# axiom_beta_plugin_module_TE0714_SDI_v0_6.net
KiCad netlist of a schematic drawn in EAGLE
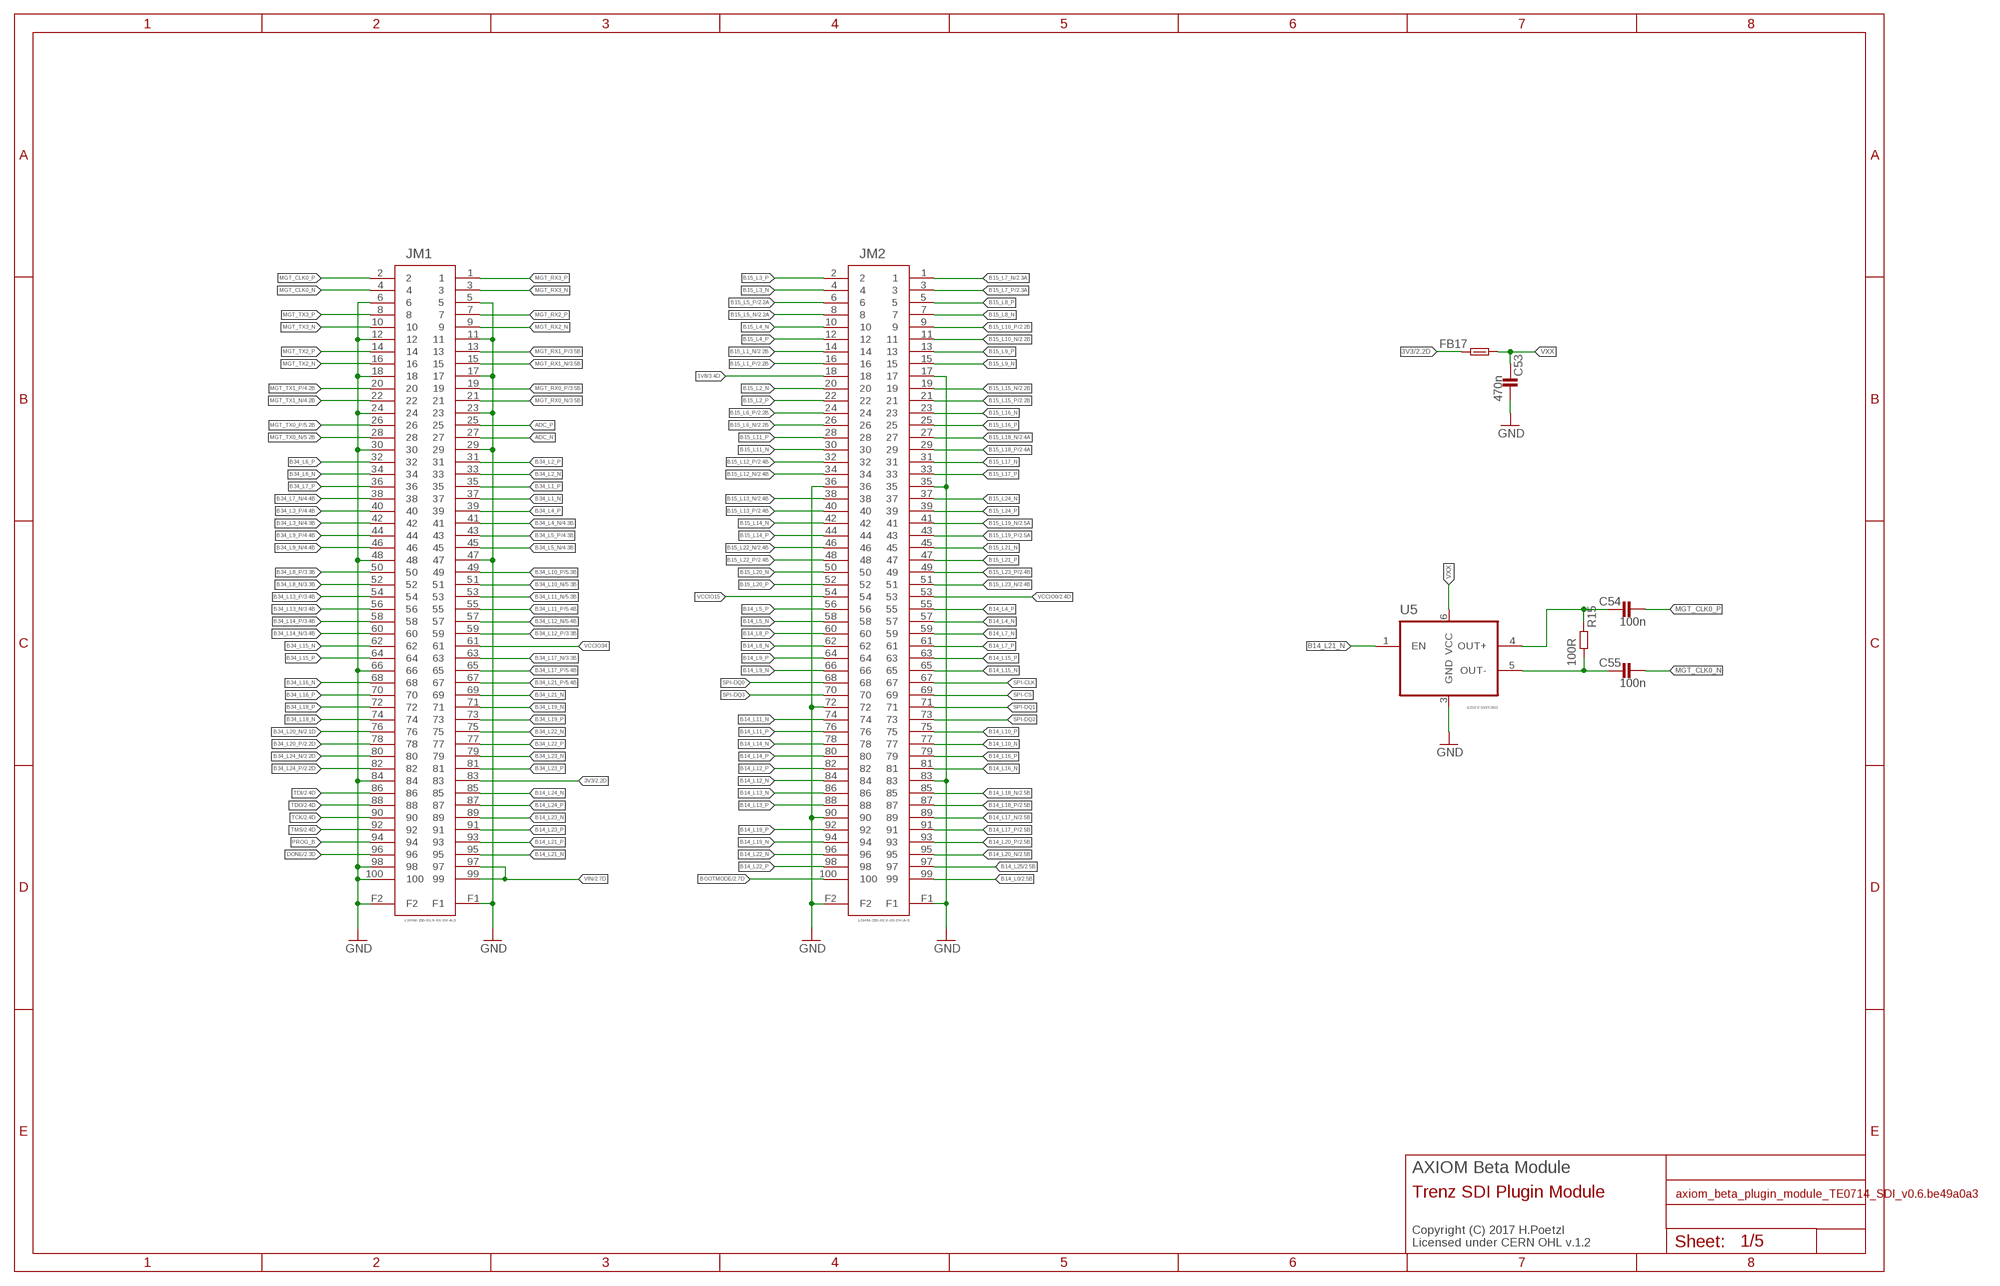
[diagram p0: schematic, sheet 1]
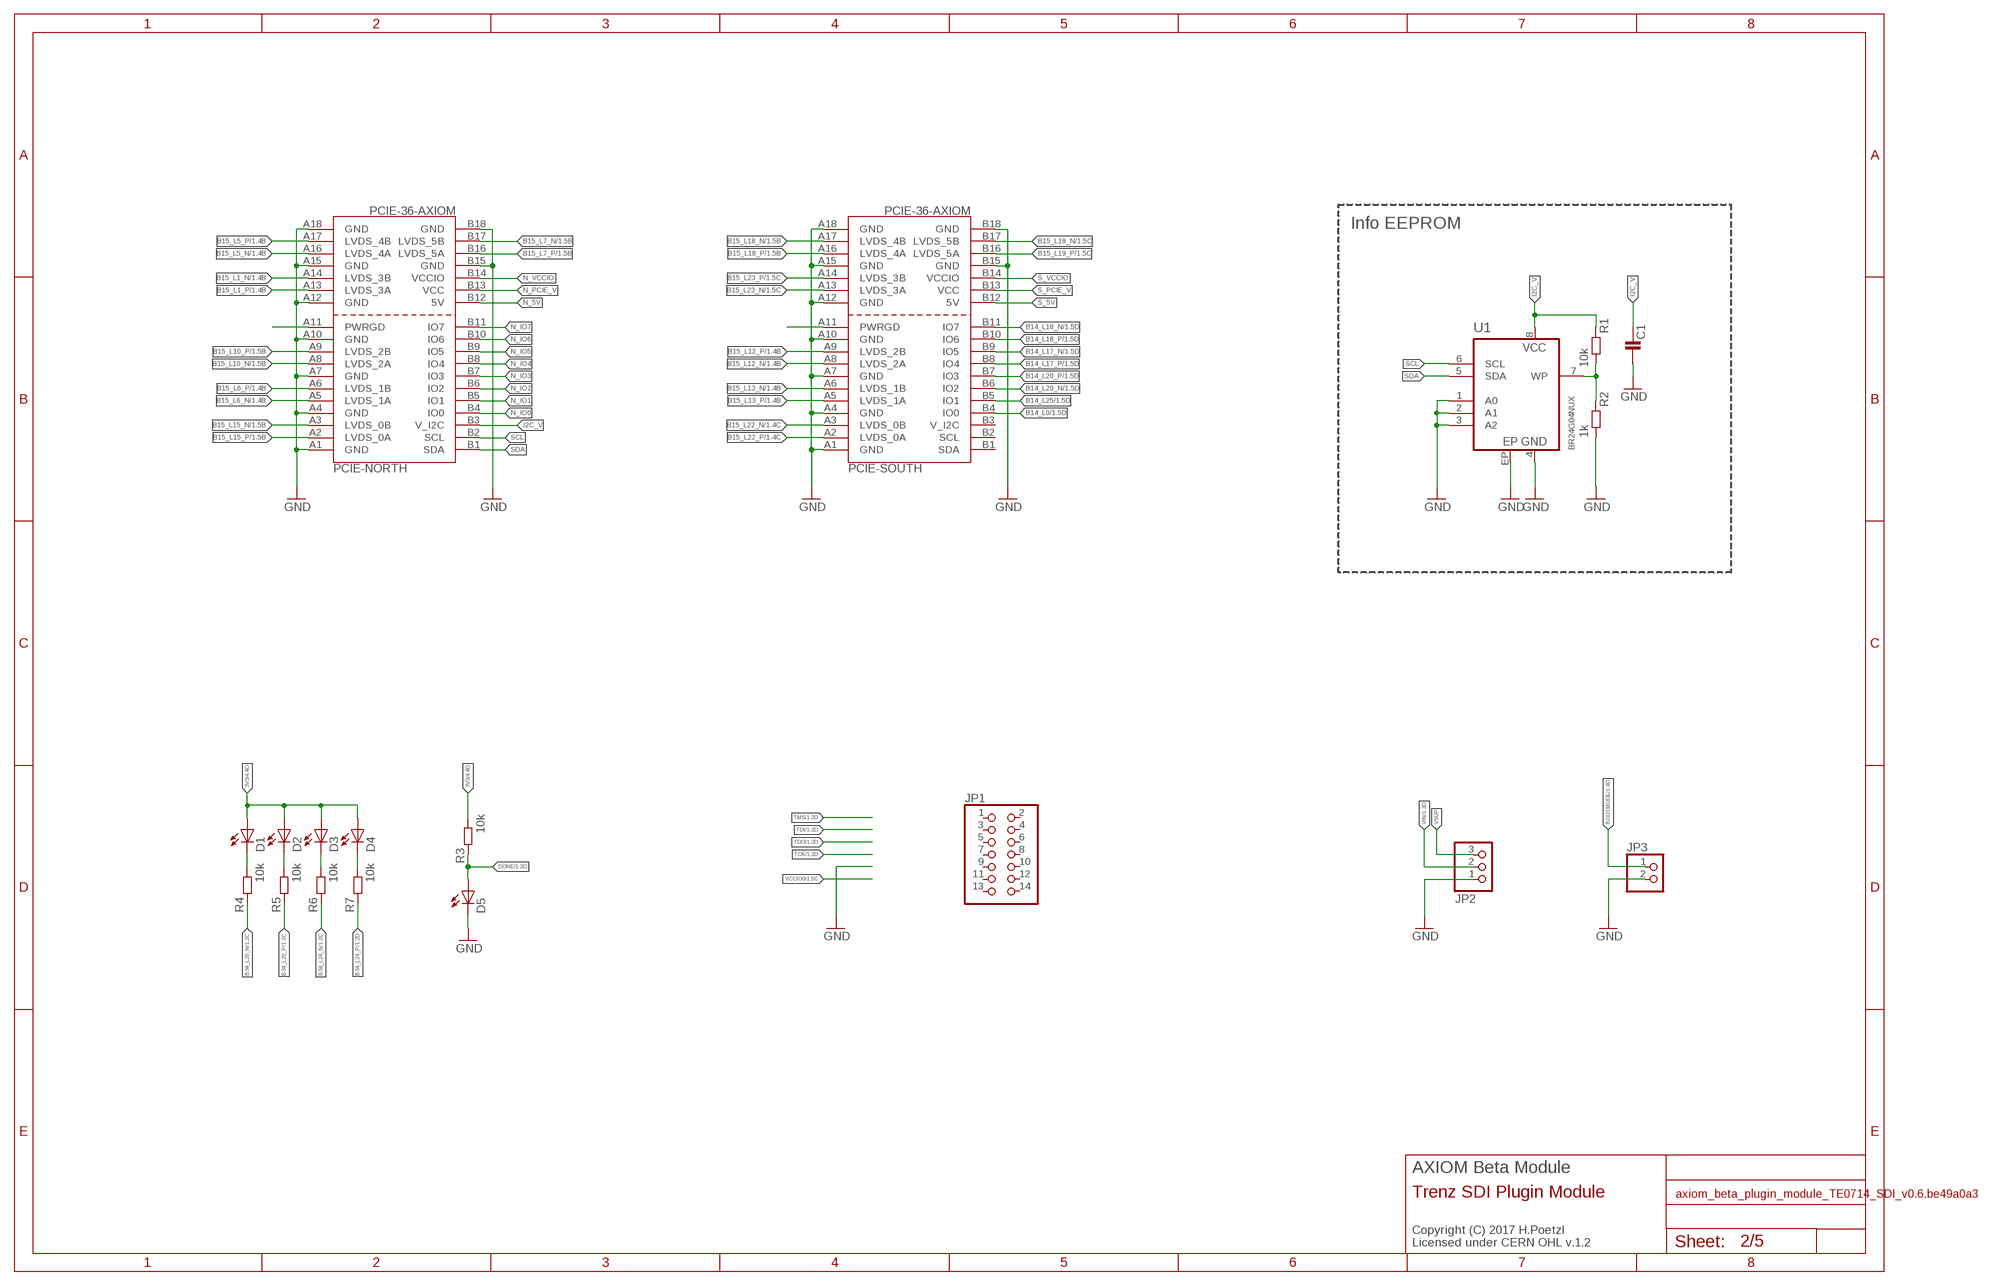
[diagram p1: schematic, sheet 2]
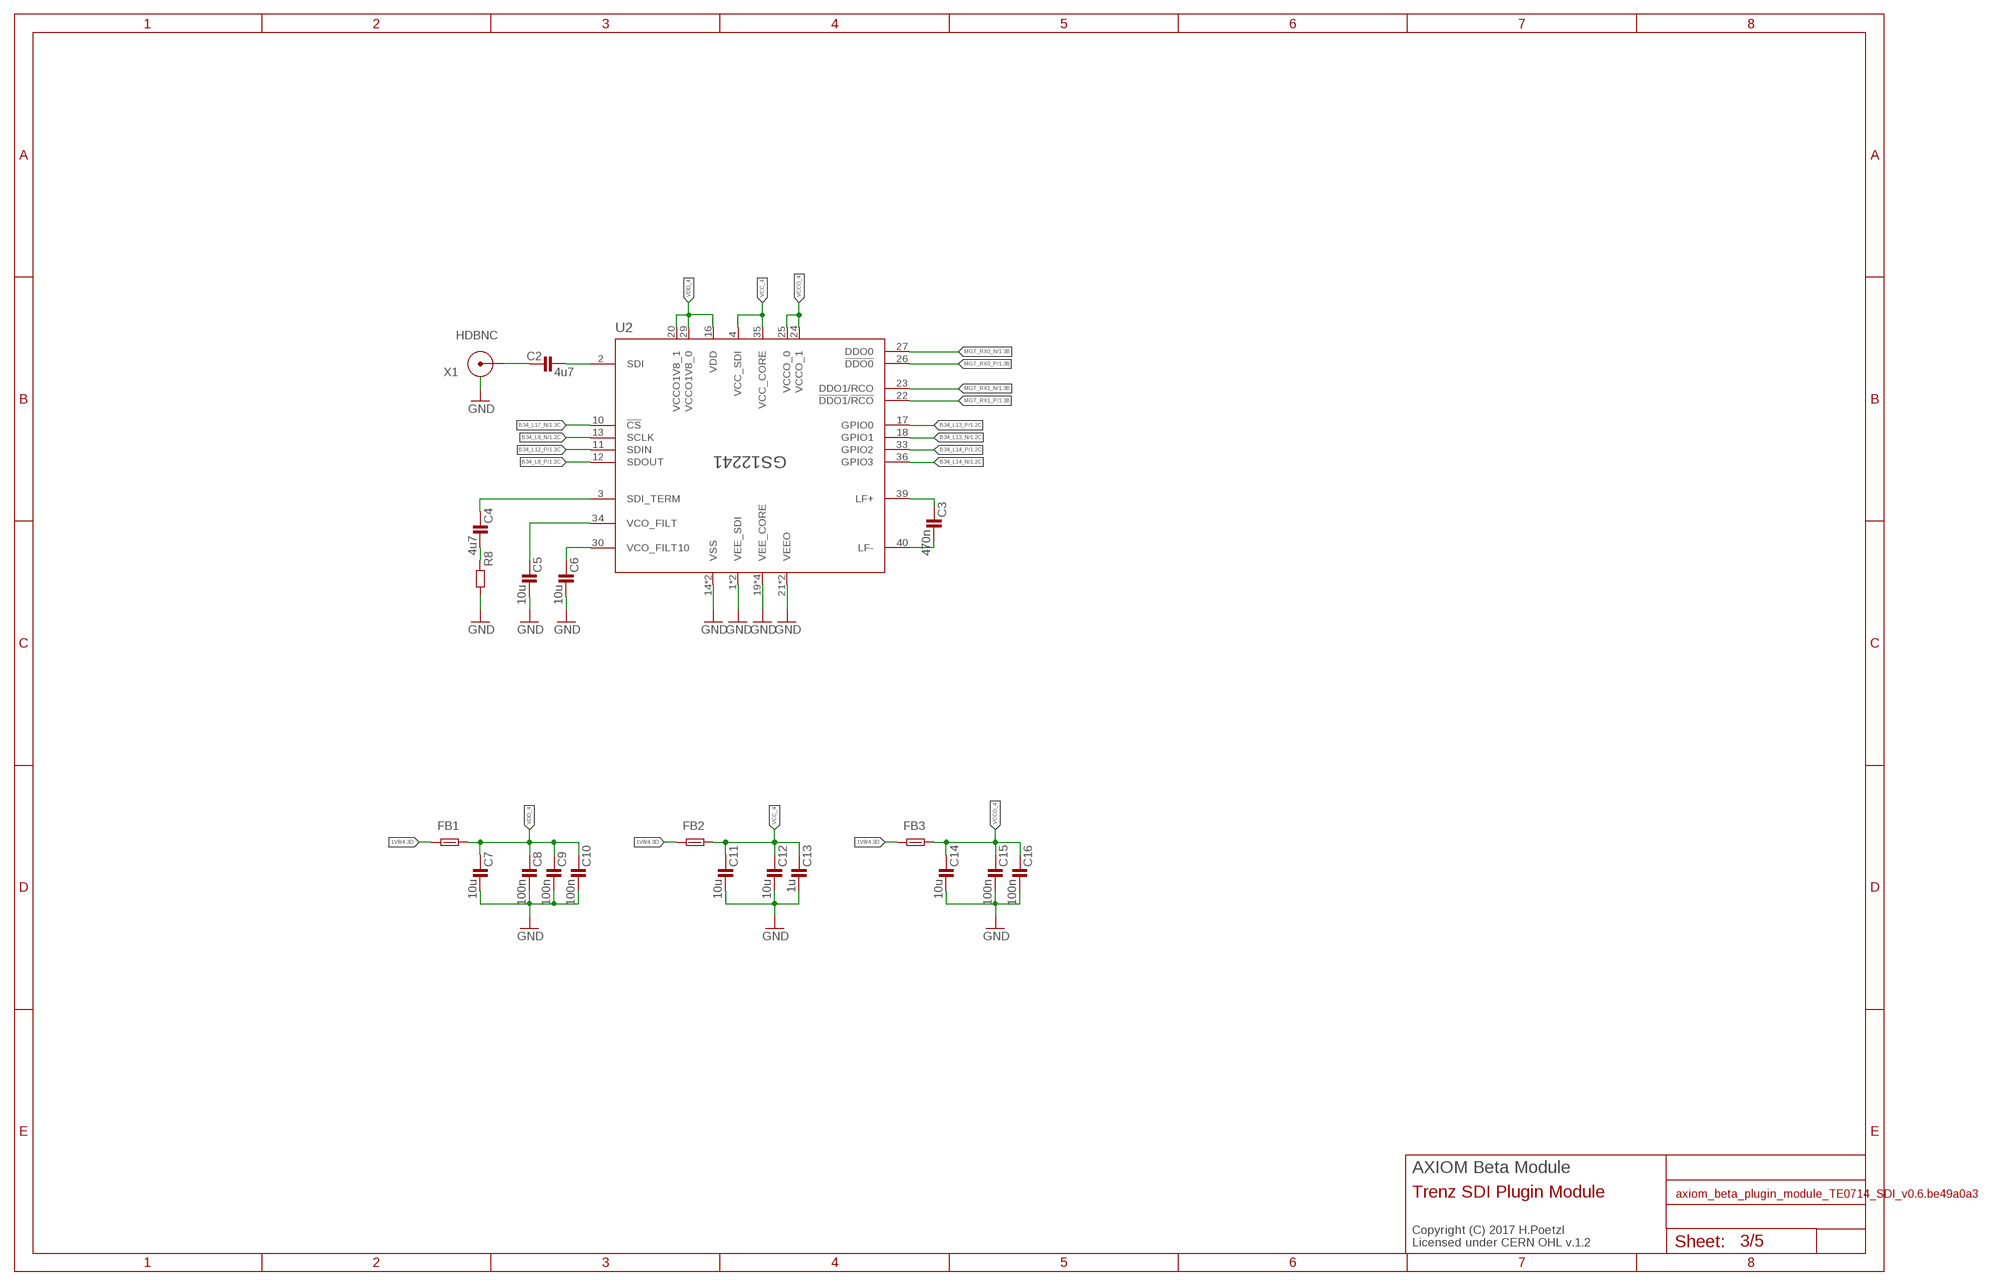
[diagram p2: schematic, sheet 3]
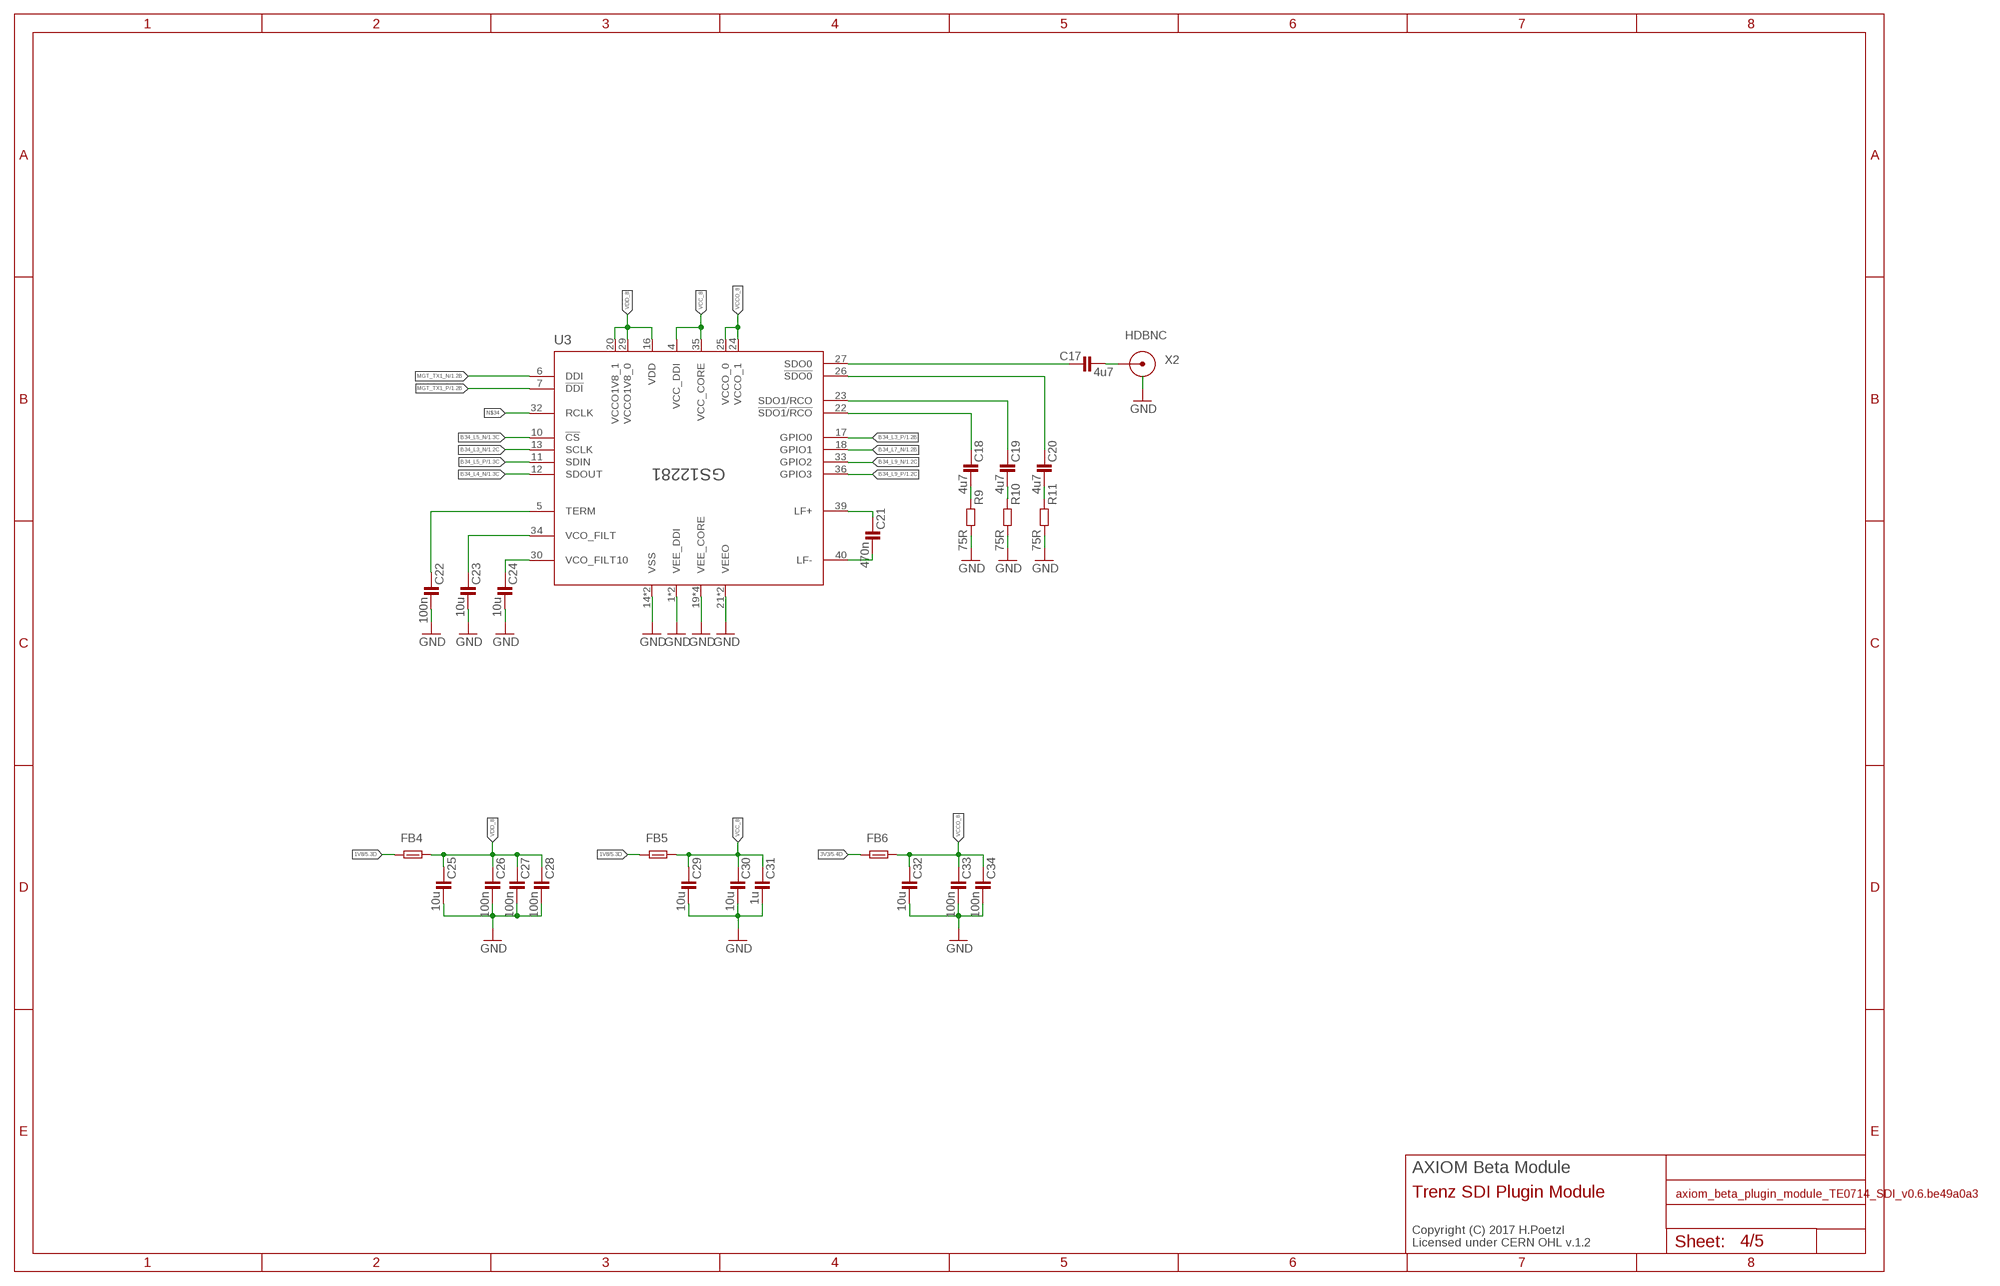
[diagram p3: schematic, sheet 4]
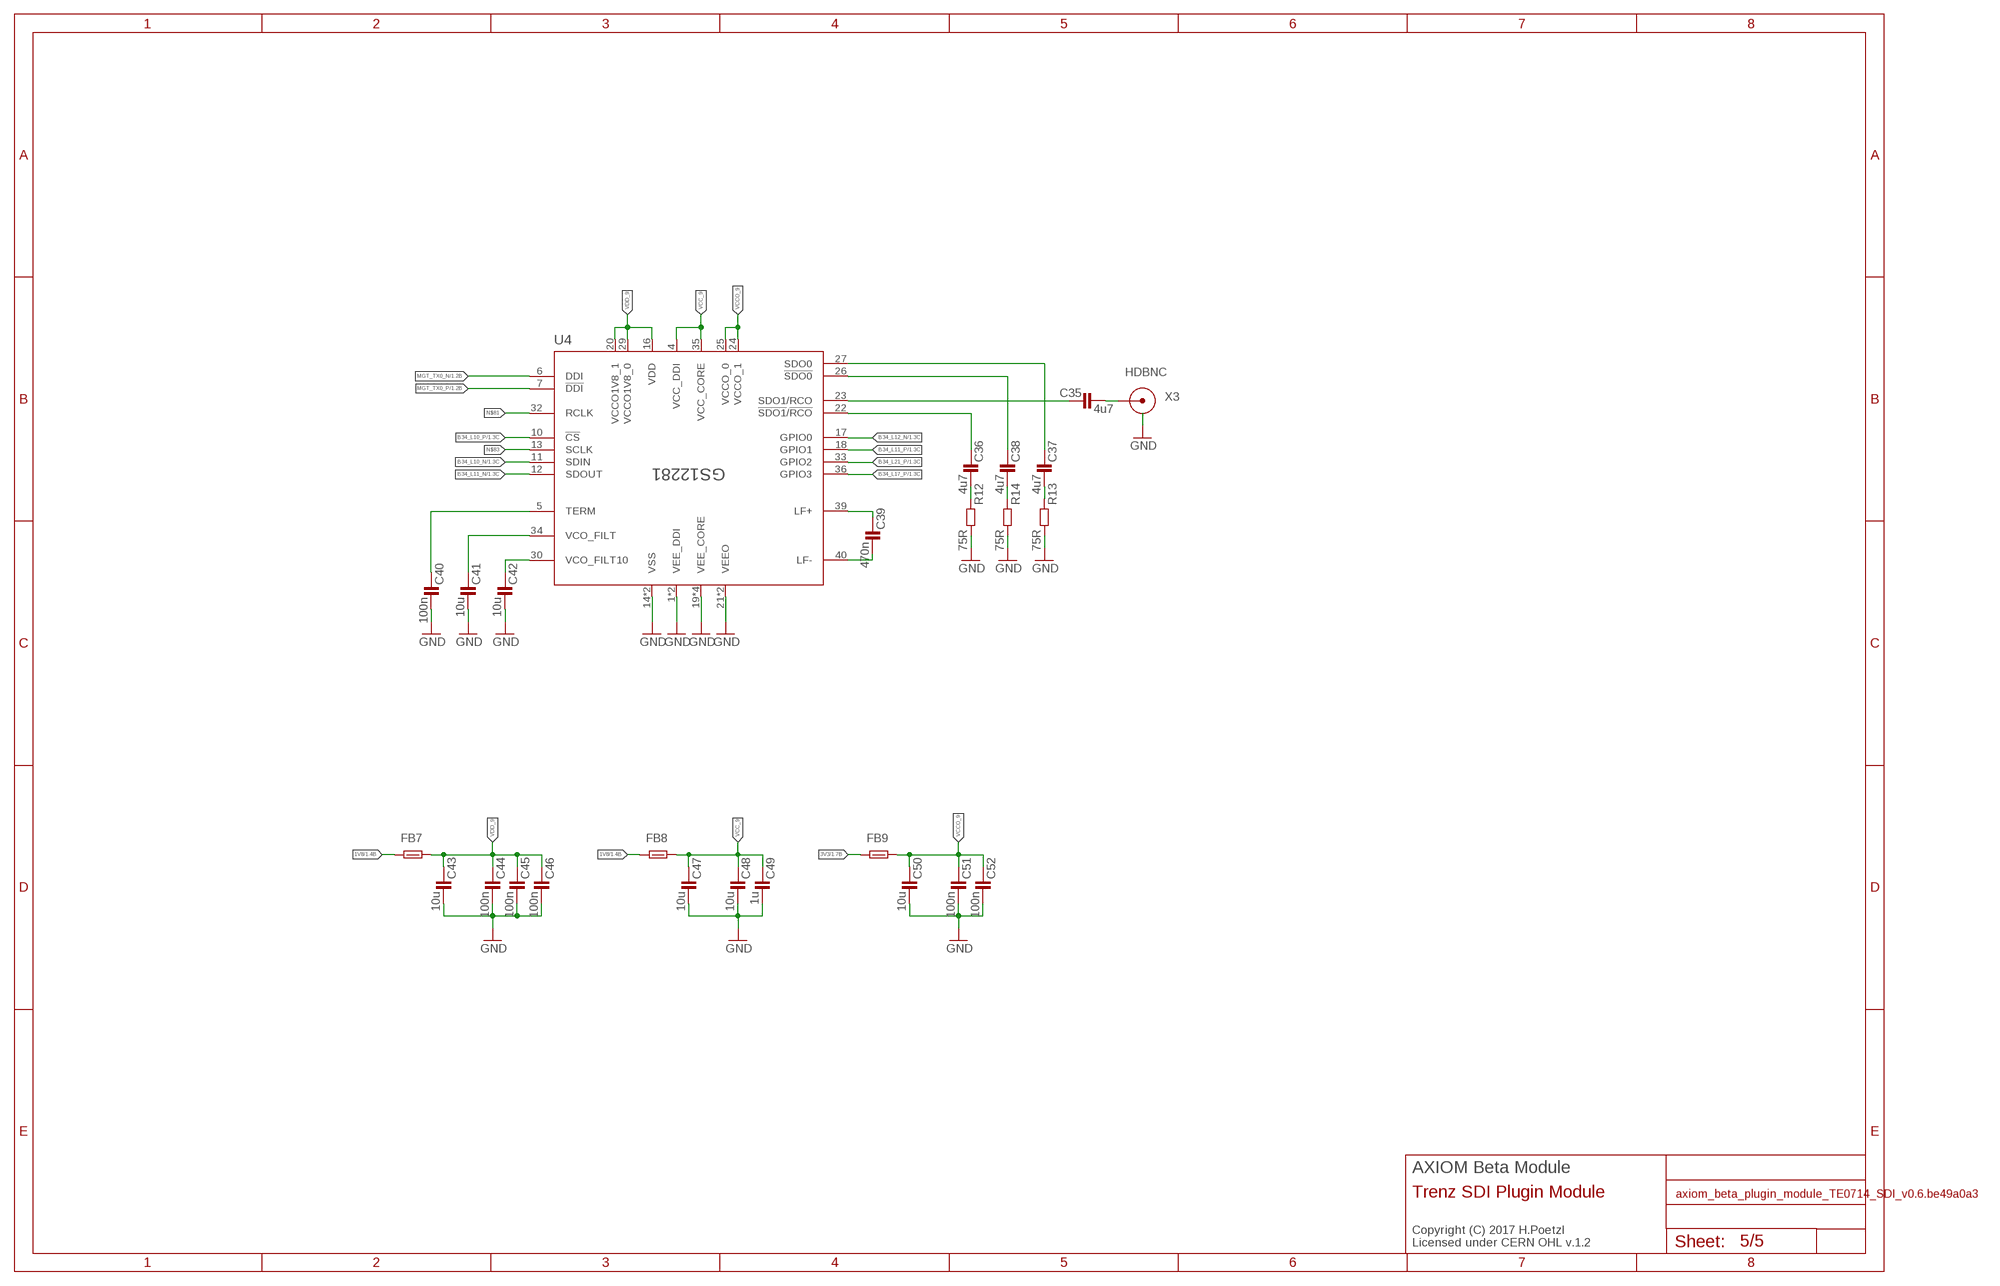
[diagram p4: schematic, sheet 5]

(export (version "E")
  (design (tool "Eeschema 10.0.6"))
  (components
    (comp (ref "C17")
      (value "4u7")
      (footprint "eagle-import:0402-C")
      (libsource (lib "eagle-import") (part "C0402-C"))
    )
    (comp (ref "C18")
      (value "4u7")
      (footprint "eagle-import:0402-C")
      (libsource (lib "eagle-import") (part "C0402-C"))
    )
    (comp (ref "C19")
      (value "4u7")
      (footprint "eagle-import:0402-C")
      (libsource (lib "eagle-import") (part "C0402-C"))
    )
    (comp (ref "C20")
      (value "4u7")
      (footprint "eagle-import:0402-C")
      (libsource (lib "eagle-import") (part "C0402-C"))
    )
    (comp (ref "C21")
      (value "470n")
      (footprint "eagle-import:0201-C")
      (libsource (lib "eagle-import") (part "C0201-C"))
    )
    (comp (ref "C22")
      (value "100n")
      (footprint "eagle-import:0201-C")
      (libsource (lib "eagle-import") (part "C0201-C"))
    )
    (comp (ref "C23")
      (value "10u")
      (footprint "eagle-import:0201-C")
      (libsource (lib "eagle-import") (part "C0201-C"))
    )
    (comp (ref "C24")
      (value "10u")
      (footprint "eagle-import:0402-C")
      (libsource (lib "eagle-import") (part "C0402-C"))
    )
    (comp (ref "C25")
      (value "10u")
      (footprint "eagle-import:0402-C")
      (libsource (lib "eagle-import") (part "C0402-C"))
    )
    (comp (ref "C26")
      (value "100n")
      (footprint "eagle-import:0201-C")
      (libsource (lib "eagle-import") (part "C0201-C"))
    )
    (comp (ref "C27")
      (value "100n")
      (footprint "eagle-import:0201-C")
      (libsource (lib "eagle-import") (part "C0201-C"))
    )
    (comp (ref "C28")
      (value "100n")
      (footprint "eagle-import:0201-C")
      (libsource (lib "eagle-import") (part "C0201-C"))
    )
    (comp (ref "C29")
      (value "10u")
      (footprint "eagle-import:0402-C")
      (libsource (lib "eagle-import") (part "C0402-C"))
    )
    (comp (ref "C30")
      (value "10u")
      (footprint "eagle-import:0402-C")
      (libsource (lib "eagle-import") (part "C0402-C"))
    )
    (comp (ref "C31")
      (value "1u")
      (footprint "eagle-import:0201-C")
      (libsource (lib "eagle-import") (part "C0201-C"))
    )
    (comp (ref "C32")
      (value "10u")
      (footprint "eagle-import:0402-C")
      (libsource (lib "eagle-import") (part "C0402-C"))
    )
    (comp (ref "C33")
      (value "100n")
      (footprint "eagle-import:0201-C")
      (libsource (lib "eagle-import") (part "C0201-C"))
    )
    (comp (ref "C34")
      (value "100n")
      (footprint "eagle-import:0201-C")
      (libsource (lib "eagle-import") (part "C0201-C"))
    )
    (comp (ref "FB4")
      (value "FB0402-C")
      (footprint "eagle-import:0402-C")
      (libsource (lib "eagle-import") (part "FB0402-C"))
    )
    (comp (ref "FB5")
      (value "FB0402-C")
      (footprint "eagle-import:0402-C")
      (libsource (lib "eagle-import") (part "FB0402-C"))
    )
    (comp (ref "FB6")
      (value "FB0402-C")
      (footprint "eagle-import:0402-C")
      (libsource (lib "eagle-import") (part "FB0402-C"))
    )
    (comp (ref "R9")
      (value "75R")
      (footprint "eagle-import:0201-C")
      (libsource (lib "eagle-import") (part "R0201-C"))
    )
    (comp (ref "R10")
      (value "75R")
      (footprint "eagle-import:0201-C")
      (libsource (lib "eagle-import") (part "R0201-C"))
    )
    (comp (ref "R11")
      (value "75R")
      (footprint "eagle-import:0201-C")
      (libsource (lib "eagle-import") (part "R0201-C"))
    )
    (comp (ref "U3")
      (value "GS12281")
      (footprint "eagle-import:UQFN40P600X400X100-41N")
      (libsource (lib "eagle-import") (part "GS12281"))
    )
    (comp (ref "X2")
      (value "HDBNC")
      (footprint "eagle-import:HDBNC_EDGE_2SIDE")
      (libsource (lib "eagle-import") (part "HDBNC"))
    )
    (comp (ref "C1")
      (value "C0402-B")
      (footprint "eagle-import:0402-B")
      (libsource (lib "eagle-import") (part "C0402-B"))
    )
    (comp (ref "D1")
      (value "LED")
      (footprint "eagle-import:SMARTLED-TTW")
      (libsource (lib "eagle-import") (part "LED"))
    )
    (comp (ref "D2")
      (value "LED")
      (footprint "eagle-import:SMARTLED-TTW")
      (libsource (lib "eagle-import") (part "LED"))
    )
    (comp (ref "D3")
      (value "LED")
      (footprint "eagle-import:SMARTLED-TTW")
      (libsource (lib "eagle-import") (part "LED"))
    )
    (comp (ref "D4")
      (value "LED")
      (footprint "eagle-import:SMARTLED-TTW")
      (libsource (lib "eagle-import") (part "LED"))
    )
    (comp (ref "D5")
      (value "LED")
      (footprint "eagle-import:SMARTLED-TTW")
      (libsource (lib "eagle-import") (part "LED"))
    )
    (comp (ref "JP1")
      (value "PINHD-2X07_2.00")
      (footprint "eagle-import:2X07M")
      (libsource (lib "eagle-import") (part "PINHD-2X07_2.00"))
    )
    (comp (ref "JP2")
      (value "PINHD-1X03_2.54-90°-S")
      (footprint "eagle-import:1X03_90-S")
      (libsource (lib "eagle-import") (part "PINHD-1X03_2.54-90°-S"))
    )
    (comp (ref "JP3")
      (value "PINHD-1X02_2.54-S")
      (footprint "eagle-import:1X02-S")
      (libsource (lib "eagle-import") (part "PINHD-1X02_2.54-S"))
    )
    (comp (ref "PCIE-NORTH")
      (value "PCIE-36-AXIOM")
      (footprint "eagle-import:PCIE-36-AXIOM")
      (libsource (lib "eagle-import") (part "PCIE-36-AXIOM"))
    )
    (comp (ref "PCIE-SOUTH")
      (value "PCIE-36-AXIOM")
      (footprint "eagle-import:PCIE-36-AXIOM")
      (libsource (lib "eagle-import") (part "PCIE-36-AXIOM"))
    )
    (comp (ref "R1")
      (value "10k")
      (footprint "eagle-import:0402-B")
      (libsource (lib "eagle-import") (part "R0402-B"))
    )
    (comp (ref "R2")
      (value "1k")
      (footprint "eagle-import:0402-B")
      (libsource (lib "eagle-import") (part "R0402-B"))
    )
    (comp (ref "R3")
      (value "10k")
      (footprint "eagle-import:0402-C")
      (libsource (lib "eagle-import") (part "R0402-C"))
    )
    (comp (ref "R4")
      (value "10k")
      (footprint "eagle-import:0402-C")
      (libsource (lib "eagle-import") (part "R0402-C"))
    )
    (comp (ref "R5")
      (value "10k")
      (footprint "eagle-import:0402-C")
      (libsource (lib "eagle-import") (part "R0402-C"))
    )
    (comp (ref "R6")
      (value "10k")
      (footprint "eagle-import:0402-C")
      (libsource (lib "eagle-import") (part "R0402-C"))
    )
    (comp (ref "R7")
      (value "10k")
      (footprint "eagle-import:0402-C")
      (libsource (lib "eagle-import") (part "R0402-C"))
    )
    (comp (ref "U1")
      (value "BR24G04NUX")
      (footprint "eagle-import:DFN200X300X100-9N")
      (libsource (lib "eagle-import") (part "BR24G04NUX"))
    )
    (comp (ref "C53")
      (value "470n")
      (footprint "eagle-import:0402-C")
      (libsource (lib "eagle-import") (part "C0402-C"))
    )
    (comp (ref "C54")
      (value "100n")
      (footprint "eagle-import:0201-C")
      (libsource (lib "eagle-import") (part "C0201-C"))
    )
    (comp (ref "C55")
      (value "100n")
      (footprint "eagle-import:0201-C")
      (libsource (lib "eagle-import") (part "C0201-C"))
    )
    (comp (ref "FB17")
      (value "FB0402-C")
      (footprint "eagle-import:0402-C")
      (libsource (lib "eagle-import") (part "FB0402-C"))
    )
    (comp (ref "JM1")
      (value "LSHM-150-XX.X-XX-DV-A-S")
      (footprint "eagle-import:LSHM-150-XX.X-XX-DV-A-S")
      (libsource (lib "eagle-import") (part "LSHM-150-XX.X-XX-DV-A-S"))
    )
    (comp (ref "JM2")
      (value "LSHM-150-XX.X-XX-DV-A-S")
      (footprint "eagle-import:LSHM-150-XX.X-XX-DV-A-S")
      (libsource (lib "eagle-import") (part "LSHM-150-XX.X-XX-DV-A-S"))
    )
    (comp (ref "R15")
      (value "100R")
      (footprint "eagle-import:0201-C")
      (libsource (lib "eagle-import") (part "R0201-C"))
    )
    (comp (ref "U5")
      (value "DSC11XX-3.2X2.5")
      (footprint "eagle-import:3.2X2.5")
      (libsource (lib "eagle-import") (part "DSC11XX-3.2X2.5"))
    )
    (comp (ref "C2")
      (value "4u7")
      (footprint "eagle-import:0402-C")
      (libsource (lib "eagle-import") (part "C0402-C"))
    )
    (comp (ref "C3")
      (value "470n")
      (footprint "eagle-import:0201-C")
      (libsource (lib "eagle-import") (part "C0201-C"))
    )
    (comp (ref "C4")
      (value "4u7")
      (footprint "eagle-import:0402-C")
      (libsource (lib "eagle-import") (part "C0402-C"))
    )
    (comp (ref "C5")
      (value "10u")
      (footprint "eagle-import:0201-C")
      (libsource (lib "eagle-import") (part "C0201-C"))
    )
    (comp (ref "C6")
      (value "10u")
      (footprint "eagle-import:0402-C")
      (libsource (lib "eagle-import") (part "C0402-C"))
    )
    (comp (ref "C7")
      (value "10u")
      (footprint "eagle-import:0402-C")
      (libsource (lib "eagle-import") (part "C0402-C"))
    )
    (comp (ref "C8")
      (value "100n")
      (footprint "eagle-import:0201-C")
      (libsource (lib "eagle-import") (part "C0201-C"))
    )
    (comp (ref "C9")
      (value "100n")
      (footprint "eagle-import:0201-C")
      (libsource (lib "eagle-import") (part "C0201-C"))
    )
    (comp (ref "C10")
      (value "100n")
      (footprint "eagle-import:0201-C")
      (libsource (lib "eagle-import") (part "C0201-C"))
    )
    (comp (ref "C11")
      (value "10u")
      (footprint "eagle-import:0402-C")
      (libsource (lib "eagle-import") (part "C0402-C"))
    )
    (comp (ref "C12")
      (value "10u")
      (footprint "eagle-import:0402-C")
      (libsource (lib "eagle-import") (part "C0402-C"))
    )
    (comp (ref "C13")
      (value "1u")
      (footprint "eagle-import:0201-C")
      (libsource (lib "eagle-import") (part "C0201-C"))
    )
    (comp (ref "C14")
      (value "10u")
      (footprint "eagle-import:0402-C")
      (libsource (lib "eagle-import") (part "C0402-C"))
    )
    (comp (ref "C15")
      (value "100n")
      (footprint "eagle-import:0201-C")
      (libsource (lib "eagle-import") (part "C0201-C"))
    )
    (comp (ref "C16")
      (value "100n")
      (footprint "eagle-import:0201-C")
      (libsource (lib "eagle-import") (part "C0201-C"))
    )
    (comp (ref "FB1")
      (value "FB0402-C")
      (footprint "eagle-import:0402-C")
      (libsource (lib "eagle-import") (part "FB0402-C"))
    )
    (comp (ref "FB2")
      (value "FB0402-C")
      (footprint "eagle-import:0402-C")
      (libsource (lib "eagle-import") (part "FB0402-C"))
    )
    (comp (ref "FB3")
      (value "FB0402-C")
      (footprint "eagle-import:0402-C")
      (libsource (lib "eagle-import") (part "FB0402-C"))
    )
    (comp (ref "R8")
      (value "R0201-C")
      (footprint "eagle-import:0201-C")
      (libsource (lib "eagle-import") (part "R0201-C"))
    )
    (comp (ref "U2")
      (value "GS12241")
      (footprint "eagle-import:UQFN40P600X400X100-41N")
      (libsource (lib "eagle-import") (part "GS12241"))
    )
    (comp (ref "X1")
      (value "HDBNC")
      (footprint "eagle-import:HDBNC_EDGE_2SIDE")
      (libsource (lib "eagle-import") (part "HDBNC"))
    )
    (comp (ref "C35")
      (value "4u7")
      (footprint "eagle-import:0402-C")
      (libsource (lib "eagle-import") (part "C0402-C"))
    )
    (comp (ref "C36")
      (value "4u7")
      (footprint "eagle-import:0402-C")
      (libsource (lib "eagle-import") (part "C0402-C"))
    )
    (comp (ref "C37")
      (value "4u7")
      (footprint "eagle-import:0402-C")
      (libsource (lib "eagle-import") (part "C0402-C"))
    )
    (comp (ref "C38")
      (value "4u7")
      (footprint "eagle-import:0402-C")
      (libsource (lib "eagle-import") (part "C0402-C"))
    )
    (comp (ref "C39")
      (value "470n")
      (footprint "eagle-import:0201-C")
      (libsource (lib "eagle-import") (part "C0201-C"))
    )
    (comp (ref "C40")
      (value "100n")
      (footprint "eagle-import:0201-C")
      (libsource (lib "eagle-import") (part "C0201-C"))
    )
    (comp (ref "C41")
      (value "10u")
      (footprint "eagle-import:0402-C")
      (libsource (lib "eagle-import") (part "C0402-C"))
    )
    (comp (ref "C42")
      (value "10u")
      (footprint "eagle-import:0402-C")
      (libsource (lib "eagle-import") (part "C0402-C"))
    )
    (comp (ref "C43")
      (value "10u")
      (footprint "eagle-import:0402-C")
      (libsource (lib "eagle-import") (part "C0402-C"))
    )
    (comp (ref "C44")
      (value "100n")
      (footprint "eagle-import:0201-C")
      (libsource (lib "eagle-import") (part "C0201-C"))
    )
    (comp (ref "C45")
      (value "100n")
      (footprint "eagle-import:0201-C")
      (libsource (lib "eagle-import") (part "C0201-C"))
    )
    (comp (ref "C46")
      (value "100n")
      (footprint "eagle-import:0201-C")
      (libsource (lib "eagle-import") (part "C0201-C"))
    )
    (comp (ref "C47")
      (value "10u")
      (footprint "eagle-import:0402-C")
      (libsource (lib "eagle-import") (part "C0402-C"))
    )
    (comp (ref "C48")
      (value "10u")
      (footprint "eagle-import:0402-C")
      (libsource (lib "eagle-import") (part "C0402-C"))
    )
    (comp (ref "C49")
      (value "1u")
      (footprint "eagle-import:0201-C")
      (libsource (lib "eagle-import") (part "C0201-C"))
    )
    (comp (ref "C50")
      (value "10u")
      (footprint "eagle-import:0402-C")
      (libsource (lib "eagle-import") (part "C0402-C"))
    )
    (comp (ref "C51")
      (value "100n")
      (footprint "eagle-import:0201-C")
      (libsource (lib "eagle-import") (part "C0201-C"))
    )
    (comp (ref "C52")
      (value "100n")
      (footprint "eagle-import:0201-C")
      (libsource (lib "eagle-import") (part "C0201-C"))
    )
    (comp (ref "FB7")
      (value "FB0402-C")
      (footprint "eagle-import:0402-C")
      (libsource (lib "eagle-import") (part "FB0402-C"))
    )
    (comp (ref "FB8")
      (value "FB0402-C")
      (footprint "eagle-import:0402-C")
      (libsource (lib "eagle-import") (part "FB0402-C"))
    )
    (comp (ref "FB9")
      (value "FB0402-C")
      (footprint "eagle-import:0402-C")
      (libsource (lib "eagle-import") (part "FB0402-C"))
    )
    (comp (ref "R12")
      (value "75R")
      (footprint "eagle-import:0201-C")
      (libsource (lib "eagle-import") (part "R0201-C"))
    )
    (comp (ref "R13")
      (value "75R")
      (footprint "eagle-import:0201-C")
      (libsource (lib "eagle-import") (part "R0201-C"))
    )
    (comp (ref "R14")
      (value "75R")
      (footprint "eagle-import:0201-C")
      (libsource (lib "eagle-import") (part "R0201-C"))
    )
    (comp (ref "U4")
      (value "GS12281")
      (footprint "eagle-import:UQFN40P600X400X100-41N")
      (libsource (lib "eagle-import") (part "GS12281"))
    )
    (comp (ref "X3")
      (value "HDBNC")
      (footprint "eagle-import:HDBNC_EDGE_2SIDE")
      (libsource (lib "eagle-import") (part "HDBNC"))
    )
  )
  (nets
    (net (code "1") (name "1V8") (class "Default")
      (node (ref "FB1") (pin "1") (pinfunction "1_1") (pintype "passive"))
      (node (ref "FB2") (pin "1") (pinfunction "1_1") (pintype "passive"))
      (node (ref "FB3") (pin "1") (pinfunction "1_1") (pintype "passive"))
      (node (ref "FB4") (pin "1") (pinfunction "1_1") (pintype "passive"))
      (node (ref "FB5") (pin "1") (pinfunction "1_1") (pintype "passive"))
      (node (ref "FB7") (pin "1") (pinfunction "1_1") (pintype "passive"))
      (node (ref "FB8") (pin "1") (pinfunction "1_1") (pintype "passive"))
      (node (ref "JM2") (pin "18") (pinfunction "18_18") (pintype "bidirectional"))
    )
    (net (code "2") (name "3V3") (class "Default")
      (node (ref "D1") (pin "A@1") (pinfunction "A_A@1") (pintype "passive"))
      (node (ref "D2") (pin "A@1") (pinfunction "A_A@1") (pintype "passive"))
      (node (ref "D3") (pin "A@1") (pinfunction "A_A@1") (pintype "passive"))
      (node (ref "D4") (pin "A@1") (pinfunction "A_A@1") (pintype "passive"))
      (node (ref "FB17") (pin "1") (pinfunction "1_1") (pintype "passive"))
      (node (ref "FB6") (pin "1") (pinfunction "1_1") (pintype "passive"))
      (node (ref "FB9") (pin "1") (pinfunction "1_1") (pintype "passive"))
      (node (ref "JM1") (pin "83") (pinfunction "83_83") (pintype "bidirectional"))
      (node (ref "R3") (pin "2") (pinfunction "2_2") (pintype "passive"))
    )
    (net (code "3") (name "ADC_N") (class "Default")
      (node (ref "JM1") (pin "27") (pinfunction "27_27") (pintype "bidirectional"))
    )
    (net (code "4") (name "ADC_P") (class "Default")
      (node (ref "JM1") (pin "25") (pinfunction "25_25") (pintype "bidirectional"))
    )
    (net (code "5") (name "B14_L0") (class "Default")
      (node (ref "JM2") (pin "99") (pinfunction "99_99") (pintype "bidirectional"))
      (node (ref "PCIE-SOUTH") (pin "B4") (pinfunction "IO0_B4") (pintype "passive"))
    )
    (net (code "6") (name "B14_L4_N") (class "Default")
      (node (ref "JM2") (pin "57") (pinfunction "57_57") (pintype "bidirectional"))
    )
    (net (code "7") (name "B14_L4_P") (class "Default")
      (node (ref "JM2") (pin "55") (pinfunction "55_55") (pintype "bidirectional"))
    )
    (net (code "8") (name "B14_L5_N") (class "Default")
      (node (ref "JM2") (pin "58") (pinfunction "58_58") (pintype "bidirectional"))
    )
    (net (code "9") (name "B14_L5_P") (class "Default")
      (node (ref "JM2") (pin "56") (pinfunction "56_56") (pintype "bidirectional"))
    )
    (net (code "10") (name "B14_L7_N") (class "Default")
      (node (ref "JM2") (pin "59") (pinfunction "59_59") (pintype "bidirectional"))
    )
    (net (code "11") (name "B14_L7_P") (class "Default")
      (node (ref "JM2") (pin "61") (pinfunction "61_61") (pintype "bidirectional"))
    )
    (net (code "12") (name "B14_L8_N") (class "Default")
      (node (ref "JM2") (pin "62") (pinfunction "62_62") (pintype "bidirectional"))
    )
    (net (code "13") (name "B14_L8_P") (class "Default")
      (node (ref "JM2") (pin "60") (pinfunction "60_60") (pintype "bidirectional"))
    )
    (net (code "14") (name "B14_L9_N") (class "Default")
      (node (ref "JM2") (pin "66") (pinfunction "66_66") (pintype "bidirectional"))
    )
    (net (code "15") (name "B14_L9_P") (class "Default")
      (node (ref "JM2") (pin "64") (pinfunction "64_64") (pintype "bidirectional"))
    )
    (net (code "16") (name "B14_L10_N") (class "Default")
      (node (ref "JM2") (pin "77") (pinfunction "77_77") (pintype "bidirectional"))
    )
    (net (code "17") (name "B14_L10_P") (class "Default")
      (node (ref "JM2") (pin "75") (pinfunction "75_75") (pintype "bidirectional"))
    )
    (net (code "18") (name "B14_L11_N") (class "Default")
      (node (ref "JM2") (pin "74") (pinfunction "74_74") (pintype "bidirectional"))
    )
    (net (code "19") (name "B14_L11_P") (class "Default")
      (node (ref "JM2") (pin "76") (pinfunction "76_76") (pintype "bidirectional"))
    )
    (net (code "20") (name "B14_L12_N") (class "Default")
      (node (ref "JM2") (pin "84") (pinfunction "84_84") (pintype "bidirectional"))
    )
    (net (code "21") (name "B14_L12_P") (class "Default")
      (node (ref "JM2") (pin "82") (pinfunction "82_82") (pintype "bidirectional"))
    )
    (net (code "22") (name "B14_L13_N") (class "Default")
      (node (ref "JM2") (pin "86") (pinfunction "86_86") (pintype "bidirectional"))
    )
    (net (code "23") (name "B14_L13_P") (class "Default")
      (node (ref "JM2") (pin "88") (pinfunction "88_88") (pintype "bidirectional"))
    )
    (net (code "24") (name "B14_L14_N") (class "Default")
      (node (ref "JM2") (pin "78") (pinfunction "78_78") (pintype "bidirectional"))
    )
    (net (code "25") (name "B14_L14_P") (class "Default")
      (node (ref "JM2") (pin "80") (pinfunction "80_80") (pintype "bidirectional"))
    )
    (net (code "26") (name "B14_L15_N") (class "Default")
      (node (ref "JM2") (pin "65") (pinfunction "65_65") (pintype "bidirectional"))
    )
    (net (code "27") (name "B14_L15_P") (class "Default")
      (node (ref "JM2") (pin "63") (pinfunction "63_63") (pintype "bidirectional"))
    )
    (net (code "28") (name "B14_L16_N") (class "Default")
      (node (ref "JM2") (pin "81") (pinfunction "81_81") (pintype "bidirectional"))
    )
    (net (code "29") (name "B14_L16_P") (class "Default")
      (node (ref "JM2") (pin "79") (pinfunction "79_79") (pintype "bidirectional"))
    )
    (net (code "30") (name "B14_L17_N") (class "Default")
      (node (ref "JM2") (pin "89") (pinfunction "89_89") (pintype "bidirectional"))
      (node (ref "PCIE-SOUTH") (pin "B9") (pinfunction "IO5_B9") (pintype "passive"))
    )
    (net (code "31") (name "B14_L17_P") (class "Default")
      (node (ref "JM2") (pin "91") (pinfunction "91_91") (pintype "bidirectional"))
      (node (ref "PCIE-SOUTH") (pin "B8") (pinfunction "IO4_B8") (pintype "passive"))
    )
    (net (code "32") (name "B14_L18_N") (class "Default")
      (node (ref "JM2") (pin "85") (pinfunction "85_85") (pintype "bidirectional"))
      (node (ref "PCIE-SOUTH") (pin "B11") (pinfunction "IO7_B11") (pintype "passive"))
    )
    (net (code "33") (name "B14_L18_P") (class "Default")
      (node (ref "JM2") (pin "87") (pinfunction "87_87") (pintype "bidirectional"))
      (node (ref "PCIE-SOUTH") (pin "B10") (pinfunction "IO6_B10") (pintype "passive"))
    )
    (net (code "34") (name "B14_L19_N") (class "Default")
      (node (ref "JM2") (pin "94") (pinfunction "94_94") (pintype "bidirectional"))
    )
    (net (code "35") (name "B14_L19_P") (class "Default")
      (node (ref "JM2") (pin "92") (pinfunction "92_92") (pintype "bidirectional"))
    )
    (net (code "36") (name "B14_L20_N") (class "Default")
      (node (ref "JM2") (pin "95") (pinfunction "95_95") (pintype "bidirectional"))
      (node (ref "PCIE-SOUTH") (pin "B6") (pinfunction "IO2_B6") (pintype "passive"))
    )
    (net (code "37") (name "B14_L20_P") (class "Default")
      (node (ref "JM2") (pin "93") (pinfunction "93_93") (pintype "bidirectional"))
      (node (ref "PCIE-SOUTH") (pin "B7") (pinfunction "IO3_B7") (pintype "passive"))
    )
    (net (code "38") (name "B14_L21_N") (class "Default")
      (node (ref "JM1") (pin "95") (pinfunction "95_95") (pintype "bidirectional"))
      (node (ref "U5") (pin "1") (pinfunction "EN_1") (pintype "input"))
    )
    (net (code "39") (name "B14_L21_P") (class "Default")
      (node (ref "JM1") (pin "93") (pinfunction "93_93") (pintype "bidirectional"))
    )
    (net (code "40") (name "B14_L22_N") (class "Default")
      (node (ref "JM2") (pin "96") (pinfunction "96_96") (pintype "bidirectional"))
    )
    (net (code "41") (name "B14_L22_P") (class "Default")
      (node (ref "JM2") (pin "98") (pinfunction "98_98") (pintype "bidirectional"))
    )
    (net (code "42") (name "B14_L23_N") (class "Default")
      (node (ref "JM1") (pin "89") (pinfunction "89_89") (pintype "bidirectional"))
    )
    (net (code "43") (name "B14_L23_P") (class "Default")
      (node (ref "JM1") (pin "91") (pinfunction "91_91") (pintype "bidirectional"))
    )
    (net (code "44") (name "B14_L24_N") (class "Default")
      (node (ref "JM1") (pin "85") (pinfunction "85_85") (pintype "bidirectional"))
    )
    (net (code "45") (name "B14_L24_P") (class "Default")
      (node (ref "JM1") (pin "87") (pinfunction "87_87") (pintype "bidirectional"))
    )
    (net (code "46") (name "B14_L25") (class "Default")
      (node (ref "JM2") (pin "97") (pinfunction "97_97") (pintype "bidirectional"))
      (node (ref "PCIE-SOUTH") (pin "B5") (pinfunction "IO1_B5") (pintype "passive"))
    )
    (net (code "47") (name "B15_L1_N") (class "Default")
      (node (ref "JM2") (pin "14") (pinfunction "14_14") (pintype "bidirectional"))
      (node (ref "PCIE-NORTH") (pin "A14") (pinfunction "LVDS_3B_A14") (pintype "passive"))
    )
    (net (code "48") (name "B15_L1_P") (class "Default")
      (node (ref "JM2") (pin "16") (pinfunction "16_16") (pintype "bidirectional"))
      (node (ref "PCIE-NORTH") (pin "A13") (pinfunction "LVDS_3A_A13") (pintype "passive"))
    )
    (net (code "49") (name "B15_L2_N") (class "Default")
      (node (ref "JM2") (pin "20") (pinfunction "20_20") (pintype "bidirectional"))
    )
    (net (code "50") (name "B15_L2_P") (class "Default")
      (node (ref "JM2") (pin "22") (pinfunction "22_22") (pintype "bidirectional"))
    )
    (net (code "51") (name "B15_L3_N") (class "Default")
      (node (ref "JM2") (pin "4") (pinfunction "4_4") (pintype "bidirectional"))
    )
    (net (code "52") (name "B15_L3_P") (class "Default")
      (node (ref "JM2") (pin "2") (pinfunction "2_2") (pintype "bidirectional"))
    )
    (net (code "53") (name "B15_L4_N") (class "Default")
      (node (ref "JM2") (pin "10") (pinfunction "10_10") (pintype "bidirectional"))
    )
    (net (code "54") (name "B15_L4_P") (class "Default")
      (node (ref "JM2") (pin "12") (pinfunction "12_12") (pintype "bidirectional"))
    )
    (net (code "55") (name "B15_L5_N") (class "Default")
      (node (ref "JM2") (pin "8") (pinfunction "8_8") (pintype "bidirectional"))
      (node (ref "PCIE-NORTH") (pin "A16") (pinfunction "LVDS_4A_A16") (pintype "passive"))
    )
    (net (code "56") (name "B15_L5_P") (class "Default")
      (node (ref "JM2") (pin "6") (pinfunction "6_6") (pintype "bidirectional"))
      (node (ref "PCIE-NORTH") (pin "A17") (pinfunction "LVDS_4B_A17") (pintype "passive"))
    )
    (net (code "57") (name "B15_L6_N") (class "Default")
      (node (ref "JM2") (pin "26") (pinfunction "26_26") (pintype "bidirectional"))
      (node (ref "PCIE-NORTH") (pin "A5") (pinfunction "LVDS_1A_A5") (pintype "passive"))
    )
    (net (code "58") (name "B15_L6_P") (class "Default")
      (node (ref "JM2") (pin "24") (pinfunction "24_24") (pintype "bidirectional"))
      (node (ref "PCIE-NORTH") (pin "A6") (pinfunction "LVDS_1B_A6") (pintype "passive"))
    )
    (net (code "59") (name "B15_L7_N") (class "Default")
      (node (ref "JM2") (pin "1") (pinfunction "1_1") (pintype "bidirectional"))
      (node (ref "PCIE-NORTH") (pin "B17") (pinfunction "LVDS_5B_B17") (pintype "passive"))
    )
    (net (code "60") (name "B15_L7_P") (class "Default")
      (node (ref "JM2") (pin "3") (pinfunction "3_3") (pintype "bidirectional"))
      (node (ref "PCIE-NORTH") (pin "B16") (pinfunction "LVDS_5A_B16") (pintype "passive"))
    )
    (net (code "61") (name "B15_L8_N") (class "Default")
      (node (ref "JM2") (pin "7") (pinfunction "7_7") (pintype "bidirectional"))
    )
    (net (code "62") (name "B15_L8_P") (class "Default")
      (node (ref "JM2") (pin "5") (pinfunction "5_5") (pintype "bidirectional"))
    )
    (net (code "63") (name "B15_L9_N") (class "Default")
      (node (ref "JM2") (pin "15") (pinfunction "15_15") (pintype "bidirectional"))
    )
    (net (code "64") (name "B15_L9_P") (class "Default")
      (node (ref "JM2") (pin "13") (pinfunction "13_13") (pintype "bidirectional"))
    )
    (net (code "65") (name "B15_L10_N") (class "Default")
      (node (ref "JM2") (pin "11") (pinfunction "11_11") (pintype "bidirectional"))
      (node (ref "PCIE-NORTH") (pin "A8") (pinfunction "LVDS_2A_A8") (pintype "passive"))
    )
    (net (code "66") (name "B15_L10_P") (class "Default")
      (node (ref "JM2") (pin "9") (pinfunction "9_9") (pintype "bidirectional"))
      (node (ref "PCIE-NORTH") (pin "A9") (pinfunction "LVDS_2B_A9") (pintype "passive"))
    )
    (net (code "67") (name "B15_L11_N") (class "Default")
      (node (ref "JM2") (pin "30") (pinfunction "30_30") (pintype "bidirectional"))
    )
    (net (code "68") (name "B15_L11_P") (class "Default")
      (node (ref "JM2") (pin "28") (pinfunction "28_28") (pintype "bidirectional"))
    )
    (net (code "69") (name "B15_L12_N") (class "Default")
      (node (ref "JM2") (pin "34") (pinfunction "34_34") (pintype "bidirectional"))
      (node (ref "PCIE-SOUTH") (pin "A8") (pinfunction "LVDS_2A_A8") (pintype "passive"))
    )
    (net (code "70") (name "B15_L12_P") (class "Default")
      (node (ref "JM2") (pin "32") (pinfunction "32_32") (pintype "bidirectional"))
      (node (ref "PCIE-SOUTH") (pin "A9") (pinfunction "LVDS_2B_A9") (pintype "passive"))
    )
    (net (code "71") (name "B15_L13_N") (class "Default")
      (node (ref "JM2") (pin "38") (pinfunction "38_38") (pintype "bidirectional"))
      (node (ref "PCIE-SOUTH") (pin "A6") (pinfunction "LVDS_1B_A6") (pintype "passive"))
    )
    (net (code "72") (name "B15_L13_P") (class "Default")
      (node (ref "JM2") (pin "40") (pinfunction "40_40") (pintype "bidirectional"))
      (node (ref "PCIE-SOUTH") (pin "A5") (pinfunction "LVDS_1A_A5") (pintype "passive"))
    )
    (net (code "73") (name "B15_L14_N") (class "Default")
      (node (ref "JM2") (pin "42") (pinfunction "42_42") (pintype "bidirectional"))
    )
    (net (code "74") (name "B15_L14_P") (class "Default")
      (node (ref "JM2") (pin "44") (pinfunction "44_44") (pintype "bidirectional"))
    )
    (net (code "75") (name "B15_L15_N") (class "Default")
      (node (ref "JM2") (pin "19") (pinfunction "19_19") (pintype "bidirectional"))
      (node (ref "PCIE-NORTH") (pin "A3") (pinfunction "LVDS_0B_A3") (pintype "passive"))
    )
    (net (code "76") (name "B15_L15_P") (class "Default")
      (node (ref "JM2") (pin "21") (pinfunction "21_21") (pintype "bidirectional"))
      (node (ref "PCIE-NORTH") (pin "A2") (pinfunction "LVDS_0A_A2") (pintype "passive"))
    )
    (net (code "77") (name "B15_L16_N") (class "Default")
      (node (ref "JM2") (pin "23") (pinfunction "23_23") (pintype "bidirectional"))
    )
    (net (code "78") (name "B15_L16_P") (class "Default")
      (node (ref "JM2") (pin "25") (pinfunction "25_25") (pintype "bidirectional"))
    )
    (net (code "79") (name "B15_L17_N") (class "Default")
      (node (ref "JM2") (pin "31") (pinfunction "31_31") (pintype "bidirectional"))
    )
    (net (code "80") (name "B15_L17_P") (class "Default")
      (node (ref "JM2") (pin "33") (pinfunction "33_33") (pintype "bidirectional"))
    )
    (net (code "81") (name "B15_L18_N") (class "Default")
      (node (ref "JM2") (pin "27") (pinfunction "27_27") (pintype "bidirectional"))
      (node (ref "PCIE-SOUTH") (pin "A17") (pinfunction "LVDS_4B_A17") (pintype "passive"))
    )
    (net (code "82") (name "B15_L18_P") (class "Default")
      (node (ref "JM2") (pin "29") (pinfunction "29_29") (pintype "bidirectional"))
      (node (ref "PCIE-SOUTH") (pin "A16") (pinfunction "LVDS_4A_A16") (pintype "passive"))
    )
    (net (code "83") (name "B15_L19_N") (class "Default")
      (node (ref "JM2") (pin "41") (pinfunction "41_41") (pintype "bidirectional"))
      (node (ref "PCIE-SOUTH") (pin "B17") (pinfunction "LVDS_5B_B17") (pintype "passive"))
    )
    (net (code "84") (name "B15_L19_P") (class "Default")
      (node (ref "JM2") (pin "43") (pinfunction "43_43") (pintype "bidirectional"))
      (node (ref "PCIE-SOUTH") (pin "B16") (pinfunction "LVDS_5A_B16") (pintype "passive"))
    )
    (net (code "85") (name "B15_L20_N") (class "Default")
      (node (ref "JM2") (pin "50") (pinfunction "50_50") (pintype "bidirectional"))
    )
    (net (code "86") (name "B15_L20_P") (class "Default")
      (node (ref "JM2") (pin "52") (pinfunction "52_52") (pintype "bidirectional"))
    )
    (net (code "87") (name "B15_L21_N") (class "Default")
      (node (ref "JM2") (pin "45") (pinfunction "45_45") (pintype "bidirectional"))
    )
    (net (code "88") (name "B15_L21_P") (class "Default")
      (node (ref "JM2") (pin "47") (pinfunction "47_47") (pintype "bidirectional"))
    )
    (net (code "89") (name "B15_L22_N") (class "Default")
      (node (ref "JM2") (pin "46") (pinfunction "46_46") (pintype "bidirectional"))
      (node (ref "PCIE-SOUTH") (pin "A3") (pinfunction "LVDS_0B_A3") (pintype "passive"))
    )
    (net (code "90") (name "B15_L22_P") (class "Default")
      (node (ref "JM2") (pin "48") (pinfunction "48_48") (pintype "bidirectional"))
      (node (ref "PCIE-SOUTH") (pin "A2") (pinfunction "LVDS_0A_A2") (pintype "passive"))
    )
    (net (code "91") (name "B15_L23_N") (class "Default")
      (node (ref "JM2") (pin "51") (pinfunction "51_51") (pintype "bidirectional"))
      (node (ref "PCIE-SOUTH") (pin "A13") (pinfunction "LVDS_3A_A13") (pintype "passive"))
    )
    (net (code "92") (name "B15_L23_P") (class "Default")
      (node (ref "JM2") (pin "49") (pinfunction "49_49") (pintype "bidirectional"))
      (node (ref "PCIE-SOUTH") (pin "A14") (pinfunction "LVDS_3B_A14") (pintype "passive"))
    )
    (net (code "93") (name "B15_L24_N") (class "Default")
      (node (ref "JM2") (pin "37") (pinfunction "37_37") (pintype "bidirectional"))
    )
    (net (code "94") (name "B15_L24_P") (class "Default")
      (node (ref "JM2") (pin "39") (pinfunction "39_39") (pintype "bidirectional"))
    )
    (net (code "95") (name "B34_L1_N") (class "Default")
      (node (ref "JM1") (pin "37") (pinfunction "37_37") (pintype "bidirectional"))
    )
    (net (code "96") (name "B34_L1_P") (class "Default")
      (node (ref "JM1") (pin "35") (pinfunction "35_35") (pintype "bidirectional"))
    )
    (net (code "97") (name "B34_L2_N") (class "Default")
      (node (ref "JM1") (pin "33") (pinfunction "33_33") (pintype "bidirectional"))
    )
    (net (code "98") (name "B34_L2_P") (class "Default")
      (node (ref "JM1") (pin "31") (pinfunction "31_31") (pintype "bidirectional"))
    )
    (net (code "99") (name "B34_L3_N") (class "Default")
      (node (ref "JM1") (pin "42") (pinfunction "42_42") (pintype "bidirectional"))
      (node (ref "U3") (pin "13") (pinfunction "SCLK_13") (pintype "input"))
    )
    (net (code "100") (name "B34_L3_P") (class "Default")
      (node (ref "JM1") (pin "40") (pinfunction "40_40") (pintype "bidirectional"))
      (node (ref "U3") (pin "17") (pinfunction "GPIO0_17") (pintype "bidirectional"))
    )
    (net (code "101") (name "B34_L4_N") (class "Default")
      (node (ref "JM1") (pin "41") (pinfunction "41_41") (pintype "bidirectional"))
      (node (ref "U3") (pin "12") (pinfunction "SDOUT_12") (pintype "output"))
    )
    (net (code "102") (name "B34_L4_P") (class "Default")
      (node (ref "JM1") (pin "39") (pinfunction "39_39") (pintype "bidirectional"))
    )
    (net (code "103") (name "B34_L5_N") (class "Default")
      (node (ref "JM1") (pin "45") (pinfunction "45_45") (pintype "bidirectional"))
      (node (ref "U3") (pin "10") (pinfunction "~{CS}_10") (pintype "input"))
    )
    (net (code "104") (name "B34_L5_P") (class "Default")
      (node (ref "JM1") (pin "43") (pinfunction "43_43") (pintype "bidirectional"))
      (node (ref "U3") (pin "11") (pinfunction "SDIN_11") (pintype "input"))
    )
    (net (code "105") (name "B34_L6_N") (class "Default")
      (node (ref "JM1") (pin "34") (pinfunction "34_34") (pintype "bidirectional"))
    )
    (net (code "106") (name "B34_L6_P") (class "Default")
      (node (ref "JM1") (pin "32") (pinfunction "32_32") (pintype "bidirectional"))
    )
    (net (code "107") (name "B34_L7_N") (class "Default")
      (node (ref "JM1") (pin "38") (pinfunction "38_38") (pintype "bidirectional"))
      (node (ref "U3") (pin "18") (pinfunction "GPIO1_18") (pintype "bidirectional"))
    )
    (net (code "108") (name "B34_L7_P") (class "Default")
      (node (ref "JM1") (pin "36") (pinfunction "36_36") (pintype "bidirectional"))
    )
    (net (code "109") (name "B34_L8_N") (class "Default")
      (node (ref "JM1") (pin "52") (pinfunction "52_52") (pintype "bidirectional"))
      (node (ref "U2") (pin "13") (pinfunction "SCLK_13") (pintype "input"))
    )
    (net (code "110") (name "B34_L8_P") (class "Default")
      (node (ref "JM1") (pin "50") (pinfunction "50_50") (pintype "bidirectional"))
      (node (ref "U2") (pin "12") (pinfunction "SDOUT_12") (pintype "output"))
    )
    (net (code "111") (name "B34_L9_N") (class "Default")
      (node (ref "JM1") (pin "46") (pinfunction "46_46") (pintype "bidirectional"))
      (node (ref "U3") (pin "33") (pinfunction "GPIO2_33") (pintype "bidirectional"))
    )
    (net (code "112") (name "B34_L9_P") (class "Default")
      (node (ref "JM1") (pin "44") (pinfunction "44_44") (pintype "bidirectional"))
      (node (ref "U3") (pin "36") (pinfunction "GPIO3_36") (pintype "bidirectional"))
    )
    (net (code "113") (name "B34_L10_N") (class "Default")
      (node (ref "JM1") (pin "51") (pinfunction "51_51") (pintype "bidirectional"))
      (node (ref "U4") (pin "11") (pinfunction "SDIN_11") (pintype "input"))
    )
    (net (code "114") (name "B34_L10_P") (class "Default")
      (node (ref "JM1") (pin "49") (pinfunction "49_49") (pintype "bidirectional"))
      (node (ref "U4") (pin "10") (pinfunction "~{CS}_10") (pintype "input"))
    )
    (net (code "115") (name "B34_L11_N") (class "Default")
      (node (ref "JM1") (pin "53") (pinfunction "53_53") (pintype "bidirectional"))
      (node (ref "U4") (pin "12") (pinfunction "SDOUT_12") (pintype "output"))
    )
    (net (code "116") (name "B34_L11_P") (class "Default")
      (node (ref "JM1") (pin "55") (pinfunction "55_55") (pintype "bidirectional"))
      (node (ref "U4") (pin "18") (pinfunction "GPIO1_18") (pintype "bidirectional"))
    )
    (net (code "117") (name "B34_L12_N") (class "Default")
      (node (ref "JM1") (pin "57") (pinfunction "57_57") (pintype "bidirectional"))
      (node (ref "U4") (pin "17") (pinfunction "GPIO0_17") (pintype "bidirectional"))
    )
    (net (code "118") (name "B34_L12_P") (class "Default")
      (node (ref "JM1") (pin "59") (pinfunction "59_59") (pintype "bidirectional"))
      (node (ref "U2") (pin "11") (pinfunction "SDIN_11") (pintype "input"))
    )
    (net (code "119") (name "B34_L13_N") (class "Default")
      (node (ref "JM1") (pin "56") (pinfunction "56_56") (pintype "bidirectional"))
      (node (ref "U2") (pin "18") (pinfunction "GPIO1_18") (pintype "bidirectional"))
    )
    (net (code "120") (name "B34_L13_P") (class "Default")
      (node (ref "JM1") (pin "54") (pinfunction "54_54") (pintype "bidirectional"))
      (node (ref "U2") (pin "17") (pinfunction "GPIO0_17") (pintype "bidirectional"))
    )
    (net (code "121") (name "B34_L14_N") (class "Default")
      (node (ref "JM1") (pin "60") (pinfunction "60_60") (pintype "bidirectional"))
      (node (ref "U2") (pin "36") (pinfunction "GPIO3_36") (pintype "bidirectional"))
    )
    (net (code "122") (name "B34_L14_P") (class "Default")
      (node (ref "JM1") (pin "58") (pinfunction "58_58") (pintype "bidirectional"))
      (node (ref "U2") (pin "33") (pinfunction "GPIO2_33") (pintype "bidirectional"))
    )
    (net (code "123") (name "B34_L15_N") (class "Default")
      (node (ref "JM1") (pin "62") (pinfunction "62_62") (pintype "bidirectional"))
    )
    (net (code "124") (name "B34_L15_P") (class "Default")
      (node (ref "JM1") (pin "64") (pinfunction "64_64") (pintype "bidirectional"))
    )
    (net (code "125") (name "B34_L16_N") (class "Default")
      (node (ref "JM1") (pin "68") (pinfunction "68_68") (pintype "bidirectional"))
    )
    (net (code "126") (name "B34_L16_P") (class "Default")
      (node (ref "JM1") (pin "70") (pinfunction "70_70") (pintype "bidirectional"))
    )
    (net (code "127") (name "B34_L17_N") (class "Default")
      (node (ref "JM1") (pin "63") (pinfunction "63_63") (pintype "bidirectional"))
      (node (ref "U2") (pin "10") (pinfunction "~{CS}_10") (pintype "input"))
    )
    (net (code "128") (name "B34_L17_P") (class "Default")
      (node (ref "JM1") (pin "65") (pinfunction "65_65") (pintype "bidirectional"))
      (node (ref "U4") (pin "36") (pinfunction "GPIO3_36") (pintype "bidirectional"))
    )
    (net (code "129") (name "B34_L18_N") (class "Default")
      (node (ref "JM1") (pin "74") (pinfunction "74_74") (pintype "bidirectional"))
    )
    (net (code "130") (name "B34_L18_P") (class "Default")
      (node (ref "JM1") (pin "72") (pinfunction "72_72") (pintype "bidirectional"))
    )
    (net (code "131") (name "B34_L19_N") (class "Default")
      (node (ref "JM1") (pin "71") (pinfunction "71_71") (pintype "bidirectional"))
    )
    (net (code "132") (name "B34_L19_P") (class "Default")
      (node (ref "JM1") (pin "73") (pinfunction "73_73") (pintype "bidirectional"))
    )
    (net (code "133") (name "B34_L20_N") (class "Default")
      (node (ref "JM1") (pin "76") (pinfunction "76_76") (pintype "bidirectional"))
      (node (ref "R4") (pin "1") (pinfunction "1_1") (pintype "passive"))
    )
    (net (code "134") (name "B34_L20_P") (class "Default")
      (node (ref "JM1") (pin "78") (pinfunction "78_78") (pintype "bidirectional"))
      (node (ref "R5") (pin "1") (pinfunction "1_1") (pintype "passive"))
    )
    (net (code "135") (name "B34_L21_N") (class "Default")
      (node (ref "JM1") (pin "69") (pinfunction "69_69") (pintype "bidirectional"))
    )
    (net (code "136") (name "B34_L21_P") (class "Default")
      (node (ref "JM1") (pin "67") (pinfunction "67_67") (pintype "bidirectional"))
      (node (ref "U4") (pin "33") (pinfunction "GPIO2_33") (pintype "bidirectional"))
    )
    (net (code "137") (name "B34_L22_N") (class "Default")
      (node (ref "JM1") (pin "75") (pinfunction "75_75") (pintype "bidirectional"))
    )
    (net (code "138") (name "B34_L22_P") (class "Default")
      (node (ref "JM1") (pin "77") (pinfunction "77_77") (pintype "bidirectional"))
    )
    (net (code "139") (name "B34_L23_N") (class "Default")
      (node (ref "JM1") (pin "79") (pinfunction "79_79") (pintype "bidirectional"))
    )
    (net (code "140") (name "B34_L23_P") (class "Default")
      (node (ref "JM1") (pin "81") (pinfunction "81_81") (pintype "bidirectional"))
    )
    (net (code "141") (name "B34_L24_N") (class "Default")
      (node (ref "JM1") (pin "80") (pinfunction "80_80") (pintype "bidirectional"))
      (node (ref "R6") (pin "1") (pinfunction "1_1") (pintype "passive"))
    )
    (net (code "142") (name "B34_L24_P") (class "Default")
      (node (ref "JM1") (pin "82") (pinfunction "82_82") (pintype "bidirectional"))
      (node (ref "R7") (pin "1") (pinfunction "1_1") (pintype "passive"))
    )
    (net (code "143") (name "BOOTMODE") (class "Default")
      (node (ref "JM2") (pin "100") (pinfunction "100_100") (pintype "bidirectional"))
      (node (ref "JP3") (pin "1") (pinfunction "1_1") (pintype "passive"))
    )
    (net (code "144") (name "DONE") (class "Default")
      (node (ref "D5") (pin "A@1") (pinfunction "A_A@1") (pintype "passive"))
      (node (ref "JM1") (pin "96") (pinfunction "96_96") (pintype "bidirectional"))
      (node (ref "R3") (pin "1") (pinfunction "1_1") (pintype "passive"))
    )
    (net (code "145") (name "GND") (class "Default")
      (node (ref "C1") (pin "2") (pinfunction "2_2") (pintype "passive"))
      (node (ref "C10") (pin "2") (pinfunction "2_2") (pintype "passive"))
      (node (ref "C11") (pin "2") (pinfunction "2_2") (pintype "passive"))
      (node (ref "C12") (pin "2") (pinfunction "2_2") (pintype "passive"))
      (node (ref "C13") (pin "2") (pinfunction "2_2") (pintype "passive"))
      (node (ref "C14") (pin "2") (pinfunction "2_2") (pintype "passive"))
      (node (ref "C15") (pin "2") (pinfunction "2_2") (pintype "passive"))
      (node (ref "C16") (pin "2") (pinfunction "2_2") (pintype "passive"))
      (node (ref "C22") (pin "2") (pinfunction "2_2") (pintype "passive"))
      (node (ref "C23") (pin "2") (pinfunction "2_2") (pintype "passive"))
      (node (ref "C24") (pin "2") (pinfunction "2_2") (pintype "passive"))
      (node (ref "C25") (pin "2") (pinfunction "2_2") (pintype "passive"))
      (node (ref "C26") (pin "2") (pinfunction "2_2") (pintype "passive"))
      (node (ref "C27") (pin "2") (pinfunction "2_2") (pintype "passive"))
      (node (ref "C28") (pin "2") (pinfunction "2_2") (pintype "passive"))
      (node (ref "C29") (pin "2") (pinfunction "2_2") (pintype "passive"))
      (node (ref "C30") (pin "2") (pinfunction "2_2") (pintype "passive"))
      (node (ref "C31") (pin "2") (pinfunction "2_2") (pintype "passive"))
      (node (ref "C32") (pin "2") (pinfunction "2_2") (pintype "passive"))
      (node (ref "C33") (pin "2") (pinfunction "2_2") (pintype "passive"))
      (node (ref "C34") (pin "2") (pinfunction "2_2") (pintype "passive"))
      (node (ref "C40") (pin "2") (pinfunction "2_2") (pintype "passive"))
      (node (ref "C41") (pin "2") (pinfunction "2_2") (pintype "passive"))
      (node (ref "C42") (pin "2") (pinfunction "2_2") (pintype "passive"))
      (node (ref "C43") (pin "2") (pinfunction "2_2") (pintype "passive"))
      (node (ref "C44") (pin "2") (pinfunction "2_2") (pintype "passive"))
      (node (ref "C45") (pin "2") (pinfunction "2_2") (pintype "passive"))
      (node (ref "C46") (pin "2") (pinfunction "2_2") (pintype "passive"))
      (node (ref "C47") (pin "2") (pinfunction "2_2") (pintype "passive"))
      (node (ref "C48") (pin "2") (pinfunction "2_2") (pintype "passive"))
      (node (ref "C49") (pin "2") (pinfunction "2_2") (pintype "passive"))
      (node (ref "C5") (pin "2") (pinfunction "2_2") (pintype "passive"))
      (node (ref "C50") (pin "2") (pinfunction "2_2") (pintype "passive"))
      (node (ref "C51") (pin "2") (pinfunction "2_2") (pintype "passive"))
      (node (ref "C52") (pin "2") (pinfunction "2_2") (pintype "passive"))
      (node (ref "C53") (pin "2") (pinfunction "2_2") (pintype "passive"))
      (node (ref "C6") (pin "2") (pinfunction "2_2") (pintype "passive"))
      (node (ref "C7") (pin "2") (pinfunction "2_2") (pintype "passive"))
      (node (ref "C8") (pin "2") (pinfunction "2_2") (pintype "passive"))
      (node (ref "C9") (pin "2") (pinfunction "2_2") (pintype "passive"))
      (node (ref "D5") (pin "C@1") (pinfunction "C_C@1") (pintype "passive"))
      (node (ref "JM1") (pin "100") (pinfunction "100_100") (pintype "bidirectional"))
      (node (ref "JM1") (pin "11") (pinfunction "11_11") (pintype "bidirectional"))
      (node (ref "JM1") (pin "12") (pinfunction "12_12") (pintype "bidirectional"))
      (node (ref "JM1") (pin "17") (pinfunction "17_17") (pintype "bidirectional"))
      (node (ref "JM1") (pin "18") (pinfunction "18_18") (pintype "bidirectional"))
      (node (ref "JM1") (pin "23") (pinfunction "23_23") (pintype "bidirectional"))
      (node (ref "JM1") (pin "24") (pinfunction "24_24") (pintype "bidirectional"))
      (node (ref "JM1") (pin "29") (pinfunction "29_29") (pintype "bidirectional"))
      (node (ref "JM1") (pin "30") (pinfunction "30_30") (pintype "bidirectional"))
      (node (ref "JM1") (pin "47") (pinfunction "47_47") (pintype "bidirectional"))
      (node (ref "JM1") (pin "48") (pinfunction "48_48") (pintype "bidirectional"))
      (node (ref "JM1") (pin "5") (pinfunction "5_5") (pintype "bidirectional"))
      (node (ref "JM1") (pin "6") (pinfunction "6_6") (pintype "bidirectional"))
      (node (ref "JM1") (pin "66") (pinfunction "66_66") (pintype "bidirectional"))
      (node (ref "JM1") (pin "84") (pinfunction "84_84") (pintype "bidirectional"))
      (node (ref "JM1") (pin "98") (pinfunction "98_98") (pintype "bidirectional"))
      (node (ref "JM1") (pin "F1") (pinfunction "F1_F1") (pintype "bidirectional"))
      (node (ref "JM1") (pin "F2") (pinfunction "F2_F2") (pintype "bidirectional"))
      (node (ref "JM2") (pin "17") (pinfunction "17_17") (pintype "bidirectional"))
      (node (ref "JM2") (pin "35") (pinfunction "35_35") (pintype "bidirectional"))
      (node (ref "JM2") (pin "36") (pinfunction "36_36") (pintype "bidirectional"))
      (node (ref "JM2") (pin "72") (pinfunction "72_72") (pintype "bidirectional"))
      (node (ref "JM2") (pin "83") (pinfunction "83_83") (pintype "bidirectional"))
      (node (ref "JM2") (pin "90") (pinfunction "90_90") (pintype "bidirectional"))
      (node (ref "JM2") (pin "F1") (pinfunction "F1_F1") (pintype "bidirectional"))
      (node (ref "JM2") (pin "F2") (pinfunction "F2_F2") (pintype "bidirectional"))
      (node (ref "JP2") (pin "1") (pinfunction "1_1") (pintype "passive"))
      (node (ref "JP3") (pin "2") (pinfunction "2_2") (pintype "passive"))
      (node (ref "PCIE-NORTH") (pin "A1") (pinfunction "GND_A1") (pintype "passive"))
      (node (ref "PCIE-NORTH") (pin "A10") (pinfunction "GND_A10") (pintype "passive"))
      (node (ref "PCIE-NORTH") (pin "A12") (pinfunction "GND_A12") (pintype "passive"))
      (node (ref "PCIE-NORTH") (pin "A15") (pinfunction "GND_A15") (pintype "passive"))
      (node (ref "PCIE-NORTH") (pin "A18") (pinfunction "GND_A18") (pintype "passive"))
      (node (ref "PCIE-NORTH") (pin "A4") (pinfunction "GND_A4") (pintype "passive"))
      (node (ref "PCIE-NORTH") (pin "A7") (pinfunction "GND_A7") (pintype "passive"))
      (node (ref "PCIE-NORTH") (pin "B15") (pinfunction "GND_B15") (pintype "passive"))
      (node (ref "PCIE-NORTH") (pin "B18") (pinfunction "GND_B18") (pintype "passive"))
      (node (ref "PCIE-SOUTH") (pin "A1") (pinfunction "GND_A1") (pintype "passive"))
      (node (ref "PCIE-SOUTH") (pin "A10") (pinfunction "GND_A10") (pintype "passive"))
      (node (ref "PCIE-SOUTH") (pin "A12") (pinfunction "GND_A12") (pintype "passive"))
      (node (ref "PCIE-SOUTH") (pin "A15") (pinfunction "GND_A15") (pintype "passive"))
      (node (ref "PCIE-SOUTH") (pin "A18") (pinfunction "GND_A18") (pintype "passive"))
      (node (ref "PCIE-SOUTH") (pin "A4") (pinfunction "GND_A4") (pintype "passive"))
      (node (ref "PCIE-SOUTH") (pin "A7") (pinfunction "GND_A7") (pintype "passive"))
      (node (ref "PCIE-SOUTH") (pin "B15") (pinfunction "GND_B15") (pintype "passive"))
      (node (ref "PCIE-SOUTH") (pin "B18") (pinfunction "GND_B18") (pintype "passive"))
      (node (ref "R10") (pin "2") (pinfunction "2_2") (pintype "passive"))
      (node (ref "R11") (pin "2") (pinfunction "2_2") (pintype "passive"))
      (node (ref "R12") (pin "2") (pinfunction "2_2") (pintype "passive"))
      (node (ref "R13") (pin "2") (pinfunction "2_2") (pintype "passive"))
      (node (ref "R14") (pin "2") (pinfunction "2_2") (pintype "passive"))
      (node (ref "R2") (pin "2") (pinfunction "2_2") (pintype "passive"))
      (node (ref "R8") (pin "2") (pinfunction "2_2") (pintype "passive"))
      (node (ref "R9") (pin "2") (pinfunction "2_2") (pintype "passive"))
      (node (ref "U1") (pin "1") (pinfunction "A0_1") (pintype "input"))
      (node (ref "U1") (pin "2") (pinfunction "A1_2") (pintype "input"))
      (node (ref "U1") (pin "3") (pinfunction "A2_3") (pintype "input"))
      (node (ref "U1") (pin "4") (pinfunction "GND_4") (pintype "passive"))
      (node (ref "U1") (pin "EP") (pinfunction "EP_EP") (pintype "passive"))
      (node (ref "U2") (pin "1") (pinfunction "VEE_SDI_1") (pintype "power_in"))
      (node (ref "U2") (pin "14") (pinfunction "VSS_14") (pintype "power_in"))
      (node (ref "U2") (pin "15") (pinfunction "VSS_15") (pintype "power_in"))
      (node (ref "U2") (pin "19") (pinfunction "VEE_CORE_19") (pintype "power_in"))
      (node (ref "U2") (pin "21") (pinfunction "VEEO_21") (pintype "power_in"))
      (node (ref "U2") (pin "28") (pinfunction "VEEO_28") (pintype "power_in"))
      (node (ref "U2") (pin "31") (pinfunction "VEE_CORE_31") (pintype "power_in"))
      (node (ref "U2") (pin "37") (pinfunction "VEE_CORE_37") (pintype "power_in"))
      (node (ref "U2") (pin "38") (pinfunction "VEE_CORE_38") (pintype "power_in"))
      (node (ref "U2") (pin "8") (pinfunction "VEE_SDI_8") (pintype "power_in"))
      (node (ref "U3") (pin "1") (pinfunction "VEE_DDI_1") (pintype "power_in"))
      (node (ref "U3") (pin "14") (pinfunction "VSS_14") (pintype "power_in"))
      (node (ref "U3") (pin "15") (pinfunction "VSS_15") (pintype "power_in"))
      (node (ref "U3") (pin "19") (pinfunction "VEE_CORE_19") (pintype "power_in"))
      (node (ref "U3") (pin "21") (pinfunction "VEEO_21") (pintype "power_in"))
      (node (ref "U3") (pin "28") (pinfunction "VEEO_28") (pintype "power_in"))
      (node (ref "U3") (pin "31") (pinfunction "VEE_CORE_31") (pintype "power_in"))
      (node (ref "U3") (pin "37") (pinfunction "VEE_CORE_37") (pintype "power_in"))
      (node (ref "U3") (pin "38") (pinfunction "VEE_CORE_38") (pintype "power_in"))
      (node (ref "U3") (pin "8") (pinfunction "VEE_DDI_8") (pintype "power_in"))
      (node (ref "U4") (pin "1") (pinfunction "VEE_DDI_1") (pintype "power_in"))
      (node (ref "U4") (pin "14") (pinfunction "VSS_14") (pintype "power_in"))
      (node (ref "U4") (pin "15") (pinfunction "VSS_15") (pintype "power_in"))
      (node (ref "U4") (pin "19") (pinfunction "VEE_CORE_19") (pintype "power_in"))
      (node (ref "U4") (pin "21") (pinfunction "VEEO_21") (pintype "power_in"))
      (node (ref "U4") (pin "28") (pinfunction "VEEO_28") (pintype "power_in"))
      (node (ref "U4") (pin "31") (pinfunction "VEE_CORE_31") (pintype "power_in"))
      (node (ref "U4") (pin "37") (pinfunction "VEE_CORE_37") (pintype "power_in"))
      (node (ref "U4") (pin "38") (pinfunction "VEE_CORE_38") (pintype "power_in"))
      (node (ref "U4") (pin "8") (pinfunction "VEE_DDI_8") (pintype "power_in"))
      (node (ref "U5") (pin "3") (pinfunction "GND_3") (pintype "passive"))
      (node (ref "X1") (pin "2@1") (pinfunction "GND_2@1") (pintype "passive"))
      (node (ref "X1") (pin "2@2") (pinfunction "GND_2@2") (pintype "passive"))
      (node (ref "X1") (pin "2@3") (pinfunction "GND_2@3") (pintype "passive"))
      (node (ref "X2") (pin "2@1") (pinfunction "GND_2@1") (pintype "passive"))
      (node (ref "X2") (pin "2@2") (pinfunction "GND_2@2") (pintype "passive"))
      (node (ref "X2") (pin "2@3") (pinfunction "GND_2@3") (pintype "passive"))
      (node (ref "X3") (pin "2@1") (pinfunction "GND_2@1") (pintype "passive"))
      (node (ref "X3") (pin "2@2") (pinfunction "GND_2@2") (pintype "passive"))
      (node (ref "X3") (pin "2@3") (pinfunction "GND_2@3") (pintype "passive"))
    )
    (net (code "146") (name "I2C_V") (class "Default")
      (node (ref "C1") (pin "1") (pinfunction "1_1") (pintype "passive"))
      (node (ref "PCIE-NORTH") (pin "B3") (pinfunction "V_I2C_B3") (pintype "passive"))
      (node (ref "R1") (pin "1") (pinfunction "1_1") (pintype "passive"))
      (node (ref "U1") (pin "8") (pinfunction "VCC_8") (pintype "power_in"))
    )
    (net (code "147") (name "MGT_CLK0_N") (class "Default")
      (node (ref "C55") (pin "2") (pinfunction "2_2") (pintype "passive"))
      (node (ref "JM1") (pin "4") (pinfunction "4_4") (pintype "bidirectional"))
    )
    (net (code "148") (name "MGT_CLK0_P") (class "Default")
      (node (ref "C54") (pin "2") (pinfunction "2_2") (pintype "passive"))
      (node (ref "JM1") (pin "2") (pinfunction "2_2") (pintype "bidirectional"))
    )
    (net (code "149") (name "MGT_RX0_N") (class "Default")
      (node (ref "JM1") (pin "21") (pinfunction "21_21") (pintype "bidirectional"))
      (node (ref "U2") (pin "27") (pinfunction "DDO0_27") (pintype "output"))
    )
    (net (code "150") (name "MGT_RX0_P") (class "Default")
      (node (ref "JM1") (pin "19") (pinfunction "19_19") (pintype "bidirectional"))
      (node (ref "U2") (pin "26") (pinfunction "~{DDO0}_26") (pintype "output"))
    )
    (net (code "151") (name "MGT_RX1_N") (class "Default")
      (node (ref "JM1") (pin "15") (pinfunction "15_15") (pintype "bidirectional"))
      (node (ref "U2") (pin "23") (pinfunction "DDO1/RCO_23") (pintype "output"))
    )
    (net (code "152") (name "MGT_RX1_P") (class "Default")
      (node (ref "JM1") (pin "13") (pinfunction "13_13") (pintype "bidirectional"))
      (node (ref "U2") (pin "22") (pinfunction "~{DDO1}/~{RCO}_22") (pintype "output"))
    )
    (net (code "153") (name "MGT_RX2_N") (class "Default")
      (node (ref "JM1") (pin "9") (pinfunction "9_9") (pintype "bidirectional"))
    )
    (net (code "154") (name "MGT_RX2_P") (class "Default")
      (node (ref "JM1") (pin "7") (pinfunction "7_7") (pintype "bidirectional"))
    )
    (net (code "155") (name "MGT_RX3_N") (class "Default")
      (node (ref "JM1") (pin "3") (pinfunction "3_3") (pintype "bidirectional"))
    )
    (net (code "156") (name "MGT_RX3_P") (class "Default")
      (node (ref "JM1") (pin "1") (pinfunction "1_1") (pintype "bidirectional"))
    )
    (net (code "157") (name "MGT_TX0_N") (class "Default")
      (node (ref "JM1") (pin "28") (pinfunction "28_28") (pintype "bidirectional"))
      (node (ref "U4") (pin "6") (pinfunction "DDI_6") (pintype "input"))
    )
    (net (code "158") (name "MGT_TX0_P") (class "Default")
      (node (ref "JM1") (pin "26") (pinfunction "26_26") (pintype "bidirectional"))
      (node (ref "U4") (pin "7") (pinfunction "~{DDI}_7") (pintype "input"))
    )
    (net (code "159") (name "MGT_TX1_N") (class "Default")
      (node (ref "JM1") (pin "22") (pinfunction "22_22") (pintype "bidirectional"))
      (node (ref "U3") (pin "6") (pinfunction "DDI_6") (pintype "input"))
    )
    (net (code "160") (name "MGT_TX1_P") (class "Default")
      (node (ref "JM1") (pin "20") (pinfunction "20_20") (pintype "bidirectional"))
      (node (ref "U3") (pin "7") (pinfunction "~{DDI}_7") (pintype "input"))
    )
    (net (code "161") (name "MGT_TX2_N") (class "Default")
      (node (ref "JM1") (pin "16") (pinfunction "16_16") (pintype "bidirectional"))
    )
    (net (code "162") (name "MGT_TX2_P") (class "Default")
      (node (ref "JM1") (pin "14") (pinfunction "14_14") (pintype "bidirectional"))
    )
    (net (code "163") (name "MGT_TX3_N") (class "Default")
      (node (ref "JM1") (pin "10") (pinfunction "10_10") (pintype "bidirectional"))
    )
    (net (code "164") (name "MGT_TX3_P") (class "Default")
      (node (ref "JM1") (pin "8") (pinfunction "8_8") (pintype "bidirectional"))
    )
    (net (code "165") (name "N$34") (class "Default")
      (node (ref "U3") (pin "32") (pinfunction "RCLK_32") (pintype "input"))
    )
    (net (code "166") (name "N$81") (class "Default")
      (node (ref "U4") (pin "32") (pinfunction "RCLK_32") (pintype "input"))
    )
    (net (code "167") (name "N$83") (class "Default")
      (node (ref "U4") (pin "13") (pinfunction "SCLK_13") (pintype "input"))
    )
    (net (code "168") (name "N_5V") (class "Default")
      (node (ref "PCIE-NORTH") (pin "B12") (pinfunction "5V_B12") (pintype "passive"))
    )
    (net (code "169") (name "N_IO0") (class "Default")
      (node (ref "PCIE-NORTH") (pin "B4") (pinfunction "IO0_B4") (pintype "passive"))
    )
    (net (code "170") (name "N_IO1") (class "Default")
      (node (ref "PCIE-NORTH") (pin "B5") (pinfunction "IO1_B5") (pintype "passive"))
    )
    (net (code "171") (name "N_IO2") (class "Default")
      (node (ref "PCIE-NORTH") (pin "B6") (pinfunction "IO2_B6") (pintype "passive"))
    )
    (net (code "172") (name "N_IO3") (class "Default")
      (node (ref "PCIE-NORTH") (pin "B7") (pinfunction "IO3_B7") (pintype "passive"))
    )
    (net (code "173") (name "N_IO4") (class "Default")
      (node (ref "PCIE-NORTH") (pin "B8") (pinfunction "IO4_B8") (pintype "passive"))
    )
    (net (code "174") (name "N_IO5") (class "Default")
      (node (ref "PCIE-NORTH") (pin "B9") (pinfunction "IO5_B9") (pintype "passive"))
    )
    (net (code "175") (name "N_IO6") (class "Default")
      (node (ref "PCIE-NORTH") (pin "B10") (pinfunction "IO6_B10") (pintype "passive"))
    )
    (net (code "176") (name "N_IO7") (class "Default")
      (node (ref "PCIE-NORTH") (pin "B11") (pinfunction "IO7_B11") (pintype "passive"))
    )
    (net (code "177") (name "N_PCIE_V") (class "Default")
      (node (ref "PCIE-NORTH") (pin "B13") (pinfunction "VCC_B13") (pintype "passive"))
    )
    (net (code "178") (name "N_VCCIO") (class "Default")
      (node (ref "PCIE-NORTH") (pin "B14") (pinfunction "VCCIO_B14") (pintype "passive"))
    )
    (net (code "179") (name "Net-(C2-Pad1)") (class "Default")
      (node (ref "C2") (pin "1") (pinfunction "1_1") (pintype "passive"))
      (node (ref "X1") (pin "1") (pinfunction "1_1") (pintype "passive"))
    )
    (net (code "180") (name "Net-(C4-Pad2)") (class "Default")
      (node (ref "C4") (pin "2") (pinfunction "2_2") (pintype "passive"))
      (node (ref "R8") (pin "1") (pinfunction "1_1") (pintype "passive"))
    )
    (net (code "181") (name "Net-(C17-Pad2)") (class "Default")
      (node (ref "C17") (pin "2") (pinfunction "2_2") (pintype "passive"))
      (node (ref "X2") (pin "1") (pinfunction "1_1") (pintype "passive"))
    )
    (net (code "182") (name "Net-(C18-Pad2)") (class "Default")
      (node (ref "C18") (pin "2") (pinfunction "2_2") (pintype "passive"))
      (node (ref "R9") (pin "1") (pinfunction "1_1") (pintype "passive"))
    )
    (net (code "183") (name "Net-(C19-Pad2)") (class "Default")
      (node (ref "C19") (pin "2") (pinfunction "2_2") (pintype "passive"))
      (node (ref "R10") (pin "1") (pinfunction "1_1") (pintype "passive"))
    )
    (net (code "184") (name "Net-(C20-Pad2)") (class "Default")
      (node (ref "C20") (pin "2") (pinfunction "2_2") (pintype "passive"))
      (node (ref "R11") (pin "1") (pinfunction "1_1") (pintype "passive"))
    )
    (net (code "185") (name "Net-(C35-Pad2)") (class "Default")
      (node (ref "C35") (pin "2") (pinfunction "2_2") (pintype "passive"))
      (node (ref "X3") (pin "1") (pinfunction "1_1") (pintype "passive"))
    )
    (net (code "186") (name "Net-(C36-Pad2)") (class "Default")
      (node (ref "C36") (pin "2") (pinfunction "2_2") (pintype "passive"))
      (node (ref "R12") (pin "1") (pinfunction "1_1") (pintype "passive"))
    )
    (net (code "187") (name "Net-(C37-Pad2)") (class "Default")
      (node (ref "C37") (pin "2") (pinfunction "2_2") (pintype "passive"))
      (node (ref "R13") (pin "1") (pinfunction "1_1") (pintype "passive"))
    )
    (net (code "188") (name "Net-(C38-Pad2)") (class "Default")
      (node (ref "C38") (pin "2") (pinfunction "2_2") (pintype "passive"))
      (node (ref "R14") (pin "1") (pinfunction "1_1") (pintype "passive"))
    )
    (net (code "189") (name "Net-(D1-C)") (class "Default")
      (node (ref "D1") (pin "C@1") (pinfunction "C_C@1") (pintype "passive"))
      (node (ref "R4") (pin "2") (pinfunction "2_2") (pintype "passive"))
    )
    (net (code "190") (name "Net-(D2-C)") (class "Default")
      (node (ref "D2") (pin "C@1") (pinfunction "C_C@1") (pintype "passive"))
      (node (ref "R5") (pin "2") (pinfunction "2_2") (pintype "passive"))
    )
    (net (code "191") (name "Net-(D3-C)") (class "Default")
      (node (ref "D3") (pin "C@1") (pinfunction "C_C@1") (pintype "passive"))
      (node (ref "R6") (pin "2") (pinfunction "2_2") (pintype "passive"))
    )
    (net (code "192") (name "Net-(D4-C)") (class "Default")
      (node (ref "D4") (pin "C@1") (pinfunction "C_C@1") (pintype "passive"))
      (node (ref "R7") (pin "2") (pinfunction "2_2") (pintype "passive"))
    )
    (net (code "193") (name "Net-(U1-WP)") (class "Default")
      (node (ref "R1") (pin "2") (pinfunction "2_2") (pintype "passive"))
      (node (ref "R2") (pin "1") (pinfunction "1_1") (pintype "passive"))
      (node (ref "U1") (pin "7") (pinfunction "WP_7") (pintype "input"))
    )
    (net (code "194") (name "Net-(U2-LF+)") (class "Default")
      (node (ref "C3") (pin "1") (pinfunction "1_1") (pintype "passive"))
      (node (ref "U2") (pin "39") (pinfunction "LF+_39") (pintype "passive"))
    )
    (net (code "195") (name "Net-(U2-LF-)") (class "Default")
      (node (ref "C3") (pin "2") (pinfunction "2_2") (pintype "passive"))
      (node (ref "U2") (pin "40") (pinfunction "LF-_40") (pintype "passive"))
    )
    (net (code "196") (name "Net-(U2-SDI)") (class "Default")
      (node (ref "C2") (pin "2") (pinfunction "2_2") (pintype "passive"))
      (node (ref "U2") (pin "2") (pinfunction "SDI_2") (pintype "input"))
    )
    (net (code "197") (name "Net-(U2-SDI_TERM)") (class "Default")
      (node (ref "C4") (pin "1") (pinfunction "1_1") (pintype "passive"))
      (node (ref "U2") (pin "3") (pinfunction "SDI_TERM_3") (pintype "passive"))
    )
    (net (code "198") (name "Net-(U2-VCO_FILT)") (class "Default")
      (node (ref "C5") (pin "1") (pinfunction "1_1") (pintype "passive"))
      (node (ref "U2") (pin "34") (pinfunction "VCO_FILT_34") (pintype "passive"))
    )
    (net (code "199") (name "Net-(U2-VCO_FILT10)") (class "Default")
      (node (ref "C6") (pin "1") (pinfunction "1_1") (pintype "passive"))
      (node (ref "U2") (pin "30") (pinfunction "VCO_FILT10_30") (pintype "passive"))
    )
    (net (code "200") (name "Net-(U3-LF+)") (class "Default")
      (node (ref "C21") (pin "1") (pinfunction "1_1") (pintype "passive"))
      (node (ref "U3") (pin "39") (pinfunction "LF+_39") (pintype "passive"))
    )
    (net (code "201") (name "Net-(U3-LF-)") (class "Default")
      (node (ref "C21") (pin "2") (pinfunction "2_2") (pintype "passive"))
      (node (ref "U3") (pin "40") (pinfunction "LF-_40") (pintype "passive"))
    )
    (net (code "202") (name "Net-(U3-SDO0)") (class "Default")
      (node (ref "C17") (pin "1") (pinfunction "1_1") (pintype "passive"))
      (node (ref "U3") (pin "27") (pinfunction "SDO0_27") (pintype "output"))
    )
    (net (code "203") (name "Net-(U3-SDO1{slash}RCO)") (class "Default")
      (node (ref "C19") (pin "1") (pinfunction "1_1") (pintype "passive"))
      (node (ref "U3") (pin "23") (pinfunction "SDO1/RCO_23") (pintype "output"))
    )
    (net (code "204") (name "Net-(U3-TERM)") (class "Default")
      (node (ref "C22") (pin "1") (pinfunction "1_1") (pintype "passive"))
      (node (ref "U3") (pin "5") (pinfunction "TERM_5") (pintype "passive"))
    )
    (net (code "205") (name "Net-(U3-VCO_FILT)") (class "Default")
      (node (ref "C23") (pin "1") (pinfunction "1_1") (pintype "passive"))
      (node (ref "U3") (pin "34") (pinfunction "VCO_FILT_34") (pintype "passive"))
    )
    (net (code "206") (name "Net-(U3-VCO_FILT10)") (class "Default")
      (node (ref "C24") (pin "1") (pinfunction "1_1") (pintype "passive"))
      (node (ref "U3") (pin "30") (pinfunction "VCO_FILT10_30") (pintype "passive"))
    )
    (net (code "207") (name "Net-(U3-~{SDO0})") (class "Default")
      (node (ref "C20") (pin "1") (pinfunction "1_1") (pintype "passive"))
      (node (ref "U3") (pin "26") (pinfunction "~{SDO0}_26") (pintype "output"))
    )
    (net (code "208") (name "Net-(U3-~{SDO1}{slash}~{RCO})") (class "Default")
      (node (ref "C18") (pin "1") (pinfunction "1_1") (pintype "passive"))
      (node (ref "U3") (pin "22") (pinfunction "~{SDO1}/~{RCO}_22") (pintype "output"))
    )
    (net (code "209") (name "Net-(U4-LF+)") (class "Default")
      (node (ref "C39") (pin "1") (pinfunction "1_1") (pintype "passive"))
      (node (ref "U4") (pin "39") (pinfunction "LF+_39") (pintype "passive"))
    )
    (net (code "210") (name "Net-(U4-LF-)") (class "Default")
      (node (ref "C39") (pin "2") (pinfunction "2_2") (pintype "passive"))
      (node (ref "U4") (pin "40") (pinfunction "LF-_40") (pintype "passive"))
    )
    (net (code "211") (name "Net-(U4-SDO0)") (class "Default")
      (node (ref "C37") (pin "1") (pinfunction "1_1") (pintype "passive"))
      (node (ref "U4") (pin "27") (pinfunction "SDO0_27") (pintype "output"))
    )
    (net (code "212") (name "Net-(U4-SDO1{slash}RCO)") (class "Default")
      (node (ref "C35") (pin "1") (pinfunction "1_1") (pintype "passive"))
      (node (ref "U4") (pin "23") (pinfunction "SDO1/RCO_23") (pintype "output"))
    )
    (net (code "213") (name "Net-(U4-TERM)") (class "Default")
      (node (ref "C40") (pin "1") (pinfunction "1_1") (pintype "passive"))
      (node (ref "U4") (pin "5") (pinfunction "TERM_5") (pintype "passive"))
    )
    (net (code "214") (name "Net-(U4-VCO_FILT)") (class "Default")
      (node (ref "C41") (pin "1") (pinfunction "1_1") (pintype "passive"))
      (node (ref "U4") (pin "34") (pinfunction "VCO_FILT_34") (pintype "passive"))
    )
    (net (code "215") (name "Net-(U4-VCO_FILT10)") (class "Default")
      (node (ref "C42") (pin "1") (pinfunction "1_1") (pintype "passive"))
      (node (ref "U4") (pin "30") (pinfunction "VCO_FILT10_30") (pintype "passive"))
    )
    (net (code "216") (name "Net-(U4-~{SDO0})") (class "Default")
      (node (ref "C38") (pin "1") (pinfunction "1_1") (pintype "passive"))
      (node (ref "U4") (pin "26") (pinfunction "~{SDO0}_26") (pintype "output"))
    )
    (net (code "217") (name "Net-(U4-~{SDO1}{slash}~{RCO})") (class "Default")
      (node (ref "C36") (pin "1") (pinfunction "1_1") (pintype "passive"))
      (node (ref "U4") (pin "22") (pinfunction "~{SDO1}/~{RCO}_22") (pintype "output"))
    )
    (net (code "218") (name "Net-(U5-OUT+)") (class "Default")
      (node (ref "C54") (pin "1") (pinfunction "1_1") (pintype "passive"))
      (node (ref "R15") (pin "1") (pinfunction "1_1") (pintype "passive"))
      (node (ref "U5") (pin "4") (pinfunction "OUT+_4") (pintype "output"))
    )
    (net (code "219") (name "Net-(U5-OUT-)") (class "Default")
      (node (ref "C55") (pin "1") (pinfunction "1_1") (pintype "passive"))
      (node (ref "R15") (pin "2") (pinfunction "2_2") (pintype "passive"))
      (node (ref "U5") (pin "5") (pinfunction "OUT-_5") (pintype "output"))
    )
    (net (code "220") (name "PROG_B") (class "Default")
      (node (ref "JM1") (pin "94") (pinfunction "94_94") (pintype "bidirectional"))
    )
    (net (code "221") (name "SCL") (class "Default")
      (node (ref "PCIE-NORTH") (pin "B2") (pinfunction "SCL_B2") (pintype "passive"))
      (node (ref "U1") (pin "6") (pinfunction "SCL_6") (pintype "input"))
    )
    (net (code "222") (name "SDA") (class "Default")
      (node (ref "PCIE-NORTH") (pin "B1") (pinfunction "SDA_B1") (pintype "passive"))
      (node (ref "U1") (pin "5") (pinfunction "SDA_5") (pintype "bidirectional"))
    )
    (net (code "223") (name "SPI-CLK") (class "Default")
      (node (ref "JM2") (pin "67") (pinfunction "67_67") (pintype "bidirectional"))
    )
    (net (code "224") (name "SPI-CS") (class "Default")
      (node (ref "JM2") (pin "69") (pinfunction "69_69") (pintype "bidirectional"))
    )
    (net (code "225") (name "SPI-DQ0") (class "Default")
      (node (ref "JM2") (pin "68") (pinfunction "68_68") (pintype "bidirectional"))
    )
    (net (code "226") (name "SPI-DQ1") (class "Default")
      (node (ref "JM2") (pin "71") (pinfunction "71_71") (pintype "bidirectional"))
    )
    (net (code "227") (name "SPI-DQ2") (class "Default")
      (node (ref "JM2") (pin "73") (pinfunction "73_73") (pintype "bidirectional"))
    )
    (net (code "228") (name "SPI-DQ3") (class "Default")
      (node (ref "JM2") (pin "70") (pinfunction "70_70") (pintype "bidirectional"))
    )
    (net (code "229") (name "S_5V") (class "Default")
      (node (ref "PCIE-SOUTH") (pin "B12") (pinfunction "5V_B12") (pintype "passive"))
    )
    (net (code "230") (name "S_PCIE_V") (class "Default")
      (node (ref "PCIE-SOUTH") (pin "B13") (pinfunction "VCC_B13") (pintype "passive"))
    )
    (net (code "231") (name "S_VCCIO") (class "Default")
      (node (ref "PCIE-SOUTH") (pin "B14") (pinfunction "VCCIO_B14") (pintype "passive"))
    )
    (net (code "232") (name "TCK") (class "Default")
      (node (ref "JM1") (pin "90") (pinfunction "90_90") (pintype "bidirectional"))
    )
    (net (code "233") (name "TDI") (class "Default")
      (node (ref "JM1") (pin "86") (pinfunction "86_86") (pintype "bidirectional"))
    )
    (net (code "234") (name "TDO") (class "Default")
      (node (ref "JM1") (pin "88") (pinfunction "88_88") (pintype "bidirectional"))
    )
    (net (code "235") (name "TMS") (class "Default")
      (node (ref "JM1") (pin "92") (pinfunction "92_92") (pintype "bidirectional"))
    )
    (net (code "236") (name "VCCIO0") (class "Default")
      (node (ref "JM2") (pin "53") (pinfunction "53_53") (pintype "bidirectional"))
    )
    (net (code "237") (name "VCCIO15") (class "Default")
      (node (ref "JM2") (pin "54") (pinfunction "54_54") (pintype "bidirectional"))
    )
    (net (code "238") (name "VCCIO34") (class "Default")
      (node (ref "JM1") (pin "61") (pinfunction "61_61") (pintype "bidirectional"))
    )
    (net (code "239") (name "VCCO_4") (class "Default")
      (node (ref "C14") (pin "1") (pinfunction "1_1") (pintype "passive"))
      (node (ref "C15") (pin "1") (pinfunction "1_1") (pintype "passive"))
      (node (ref "C16") (pin "1") (pinfunction "1_1") (pintype "passive"))
      (node (ref "FB3") (pin "2") (pinfunction "2_2") (pintype "passive"))
      (node (ref "U2") (pin "24") (pinfunction "VCCO_1_24") (pintype "power_in"))
      (node (ref "U2") (pin "25") (pinfunction "VCCO_0_25") (pintype "power_in"))
    )
    (net (code "240") (name "VCCO_8") (class "Default")
      (node (ref "C32") (pin "1") (pinfunction "1_1") (pintype "passive"))
      (node (ref "C33") (pin "1") (pinfunction "1_1") (pintype "passive"))
      (node (ref "C34") (pin "1") (pinfunction "1_1") (pintype "passive"))
      (node (ref "FB6") (pin "2") (pinfunction "2_2") (pintype "passive"))
      (node (ref "U3") (pin "24") (pinfunction "VCCO_1_24") (pintype "power_in"))
      (node (ref "U3") (pin "25") (pinfunction "VCCO_0_25") (pintype "power_in"))
    )
    (net (code "241") (name "VCCO_9") (class "Default")
      (node (ref "C50") (pin "1") (pinfunction "1_1") (pintype "passive"))
      (node (ref "C51") (pin "1") (pinfunction "1_1") (pintype "passive"))
      (node (ref "C52") (pin "1") (pinfunction "1_1") (pintype "passive"))
      (node (ref "FB9") (pin "2") (pinfunction "2_2") (pintype "passive"))
      (node (ref "U4") (pin "24") (pinfunction "VCCO_1_24") (pintype "power_in"))
      (node (ref "U4") (pin "25") (pinfunction "VCCO_0_25") (pintype "power_in"))
    )
    (net (code "242") (name "VCC_4") (class "Default")
      (node (ref "C11") (pin "1") (pinfunction "1_1") (pintype "passive"))
      (node (ref "C12") (pin "1") (pinfunction "1_1") (pintype "passive"))
      (node (ref "C13") (pin "1") (pinfunction "1_1") (pintype "passive"))
      (node (ref "FB2") (pin "2") (pinfunction "2_2") (pintype "passive"))
      (node (ref "U2") (pin "35") (pinfunction "VCC_CORE_35") (pintype "power_in"))
      (node (ref "U2") (pin "4") (pinfunction "VCC_SDI_4") (pintype "power_in"))
    )
    (net (code "243") (name "VCC_8") (class "Default")
      (node (ref "C29") (pin "1") (pinfunction "1_1") (pintype "passive"))
      (node (ref "C30") (pin "1") (pinfunction "1_1") (pintype "passive"))
      (node (ref "C31") (pin "1") (pinfunction "1_1") (pintype "passive"))
      (node (ref "FB5") (pin "2") (pinfunction "2_2") (pintype "passive"))
      (node (ref "U3") (pin "35") (pinfunction "VCC_CORE_35") (pintype "power_in"))
      (node (ref "U3") (pin "4") (pinfunction "VCC_DDI_4") (pintype "power_in"))
    )
    (net (code "244") (name "VCC_9") (class "Default")
      (node (ref "C47") (pin "1") (pinfunction "1_1") (pintype "passive"))
      (node (ref "C48") (pin "1") (pinfunction "1_1") (pintype "passive"))
      (node (ref "C49") (pin "1") (pinfunction "1_1") (pintype "passive"))
      (node (ref "FB8") (pin "2") (pinfunction "2_2") (pintype "passive"))
      (node (ref "U4") (pin "35") (pinfunction "VCC_CORE_35") (pintype "power_in"))
      (node (ref "U4") (pin "4") (pinfunction "VCC_DDI_4") (pintype "power_in"))
    )
    (net (code "245") (name "VDD_4") (class "Default")
      (node (ref "C10") (pin "1") (pinfunction "1_1") (pintype "passive"))
      (node (ref "C7") (pin "1") (pinfunction "1_1") (pintype "passive"))
      (node (ref "C8") (pin "1") (pinfunction "1_1") (pintype "passive"))
      (node (ref "C9") (pin "1") (pinfunction "1_1") (pintype "passive"))
      (node (ref "FB1") (pin "2") (pinfunction "2_2") (pintype "passive"))
      (node (ref "U2") (pin "16") (pinfunction "VDD_16") (pintype "power_in"))
      (node (ref "U2") (pin "20") (pinfunction "VCCO1V8_1_20") (pintype "power_in"))
      (node (ref "U2") (pin "29") (pinfunction "VCCO1V8_0_29") (pintype "power_in"))
    )
    (net (code "246") (name "VDD_8") (class "Default")
      (node (ref "C25") (pin "1") (pinfunction "1_1") (pintype "passive"))
      (node (ref "C26") (pin "1") (pinfunction "1_1") (pintype "passive"))
      (node (ref "C27") (pin "1") (pinfunction "1_1") (pintype "passive"))
      (node (ref "C28") (pin "1") (pinfunction "1_1") (pintype "passive"))
      (node (ref "FB4") (pin "2") (pinfunction "2_2") (pintype "passive"))
      (node (ref "U3") (pin "16") (pinfunction "VDD_16") (pintype "power_in"))
      (node (ref "U3") (pin "20") (pinfunction "VCCO1V8_1_20") (pintype "power_in"))
      (node (ref "U3") (pin "29") (pinfunction "VCCO1V8_0_29") (pintype "power_in"))
    )
    (net (code "247") (name "VDD_9") (class "Default")
      (node (ref "C43") (pin "1") (pinfunction "1_1") (pintype "passive"))
      (node (ref "C44") (pin "1") (pinfunction "1_1") (pintype "passive"))
      (node (ref "C45") (pin "1") (pinfunction "1_1") (pintype "passive"))
      (node (ref "C46") (pin "1") (pinfunction "1_1") (pintype "passive"))
      (node (ref "FB7") (pin "2") (pinfunction "2_2") (pintype "passive"))
      (node (ref "U4") (pin "16") (pinfunction "VDD_16") (pintype "power_in"))
      (node (ref "U4") (pin "20") (pinfunction "VCCO1V8_1_20") (pintype "power_in"))
      (node (ref "U4") (pin "29") (pinfunction "VCCO1V8_0_29") (pintype "power_in"))
    )
    (net (code "248") (name "VIN") (class "Default")
      (node (ref "JM1") (pin "97") (pinfunction "97_97") (pintype "bidirectional"))
      (node (ref "JM1") (pin "99") (pinfunction "99_99") (pintype "bidirectional"))
      (node (ref "JP2") (pin "2") (pinfunction "2_2") (pintype "passive"))
    )
    (net (code "249") (name "VSUP") (class "Default")
      (node (ref "JP2") (pin "3") (pinfunction "3_3") (pintype "passive"))
    )
    (net (code "250") (name "VXX") (class "Default")
      (node (ref "C53") (pin "1") (pinfunction "1_1") (pintype "passive"))
      (node (ref "FB17") (pin "2") (pinfunction "2_2") (pintype "passive"))
      (node (ref "U5") (pin "6") (pinfunction "VCC_6") (pintype "power_in"))
    )
    (net (code "251") (name "unconnected-(JP1-Pad1)") (class "Default")
      (node (ref "JP1") (pin "1") (pinfunction "1_1") (pintype "passive"))
    )
    (net (code "252") (name "unconnected-(JP1-Pad2)") (class "Default")
      (node (ref "JP1") (pin "2") (pinfunction "2_2") (pintype "passive"))
    )
    (net (code "253") (name "unconnected-(JP1-Pad3)") (class "Default")
      (node (ref "JP1") (pin "3") (pinfunction "3_3") (pintype "passive"))
    )
    (net (code "254") (name "unconnected-(JP1-Pad4)") (class "Default")
      (node (ref "JP1") (pin "4") (pinfunction "4_4") (pintype "passive"))
    )
    (net (code "255") (name "unconnected-(JP1-Pad5)") (class "Default")
      (node (ref "JP1") (pin "5") (pinfunction "5_5") (pintype "passive"))
    )
    (net (code "256") (name "unconnected-(JP1-Pad6)") (class "Default")
      (node (ref "JP1") (pin "6") (pinfunction "6_6") (pintype "passive"))
    )
    (net (code "257") (name "unconnected-(JP1-Pad7)") (class "Default")
      (node (ref "JP1") (pin "7") (pinfunction "7_7") (pintype "passive"))
    )
    (net (code "258") (name "unconnected-(JP1-Pad8)") (class "Default")
      (node (ref "JP1") (pin "8") (pinfunction "8_8") (pintype "passive"))
    )
    (net (code "259") (name "unconnected-(JP1-Pad9)") (class "Default")
      (node (ref "JP1") (pin "9") (pinfunction "9_9") (pintype "passive"))
    )
    (net (code "260") (name "unconnected-(JP1-Pad10)") (class "Default")
      (node (ref "JP1") (pin "10") (pinfunction "10_10") (pintype "passive"))
    )
    (net (code "261") (name "unconnected-(JP1-Pad11)") (class "Default")
      (node (ref "JP1") (pin "11") (pinfunction "11_11") (pintype "passive"))
    )
    (net (code "262") (name "unconnected-(JP1-Pad12)") (class "Default")
      (node (ref "JP1") (pin "12") (pinfunction "12_12") (pintype "passive"))
    )
    (net (code "263") (name "unconnected-(JP1-Pad13)") (class "Default")
      (node (ref "JP1") (pin "13") (pinfunction "13_13") (pintype "passive"))
    )
    (net (code "264") (name "unconnected-(JP1-Pad14)") (class "Default")
      (node (ref "JP1") (pin "14") (pinfunction "14_14") (pintype "passive"))
    )
    (net (code "265") (name "unconnected-(PCIE-NORTH-PWRGD-PadA11)") (class "Default")
      (node (ref "PCIE-NORTH") (pin "A11") (pinfunction "PWRGD_A11") (pintype "passive"))
    )
    (net (code "266") (name "unconnected-(PCIE-SOUTH-PWRGD-PadA11)") (class "Default")
      (node (ref "PCIE-SOUTH") (pin "A11") (pinfunction "PWRGD_A11") (pintype "passive"))
    )
    (net (code "267") (name "unconnected-(PCIE-SOUTH-SCL-PadB2)") (class "Default")
      (node (ref "PCIE-SOUTH") (pin "B2") (pinfunction "SCL_B2") (pintype "passive"))
    )
    (net (code "268") (name "unconnected-(PCIE-SOUTH-SDA-PadB1)") (class "Default")
      (node (ref "PCIE-SOUTH") (pin "B1") (pinfunction "SDA_B1") (pintype "passive"))
    )
    (net (code "269") (name "unconnected-(PCIE-SOUTH-V_I2C-PadB3)") (class "Default")
      (node (ref "PCIE-SOUTH") (pin "B3") (pinfunction "V_I2C_B3") (pintype "passive"))
    )
  )
)
